# FMC.net
KiCad netlist of a schematic drawn in Altium Designer
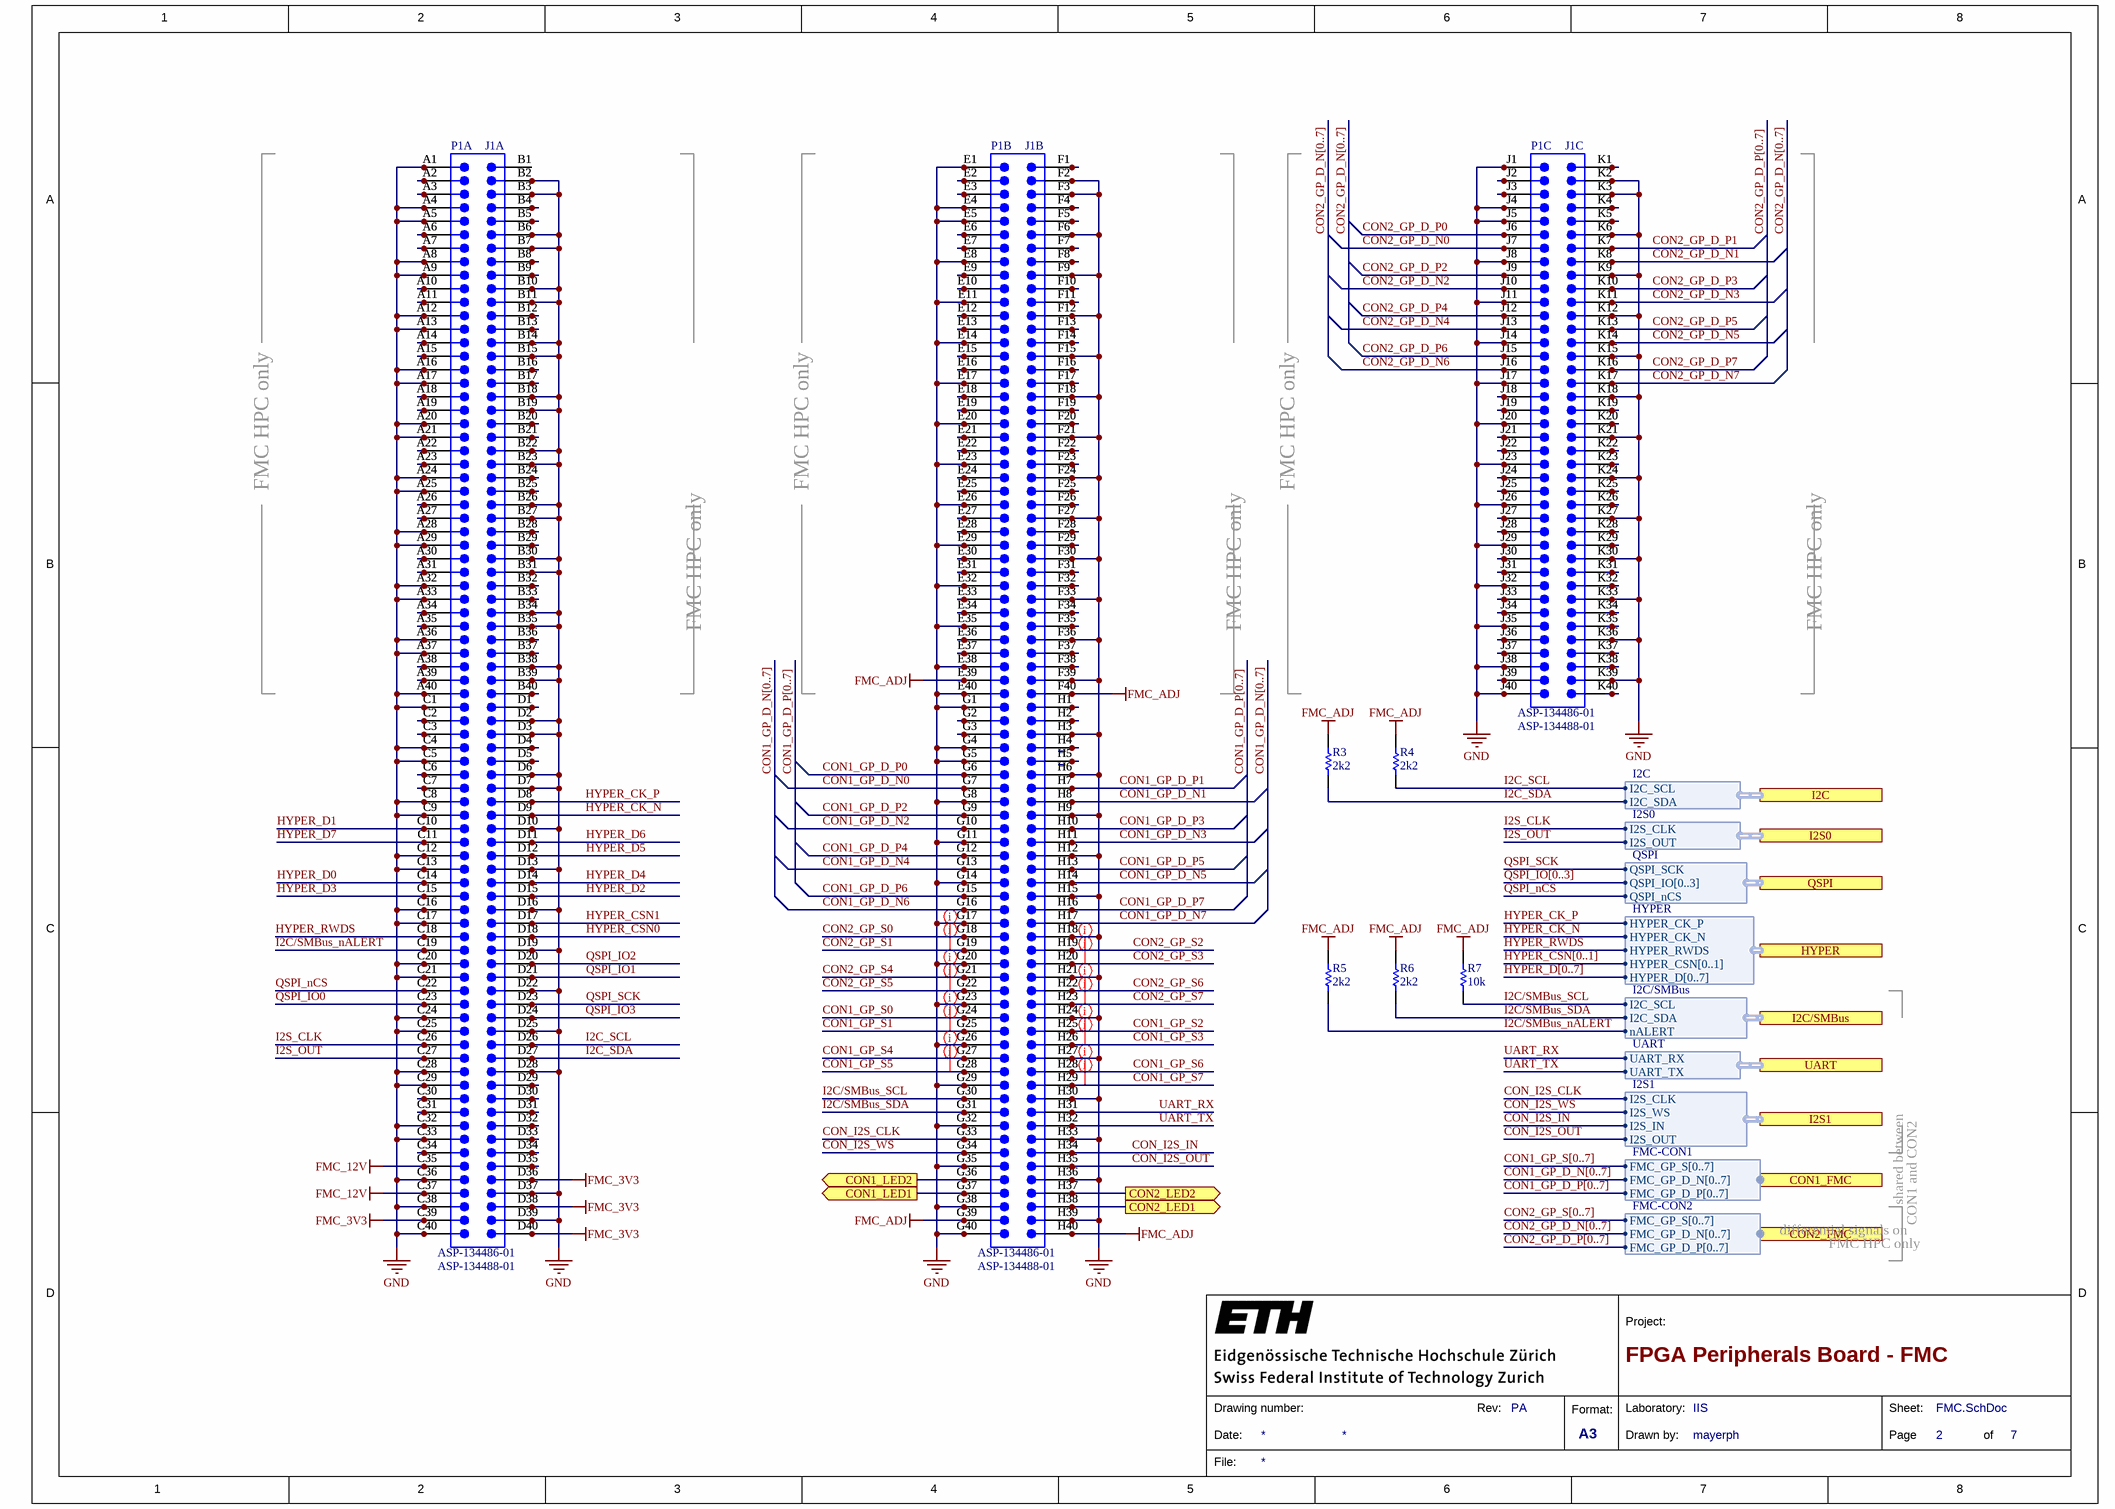
[diagram p0: FMC.SchDoc]

(export (version "E")
  (design (tool "Eeschema 10.0.6"))
  (components
    (comp (ref "J1")
      (value "ASP-134486-01")
      (footprint "BTB-SM1-27-2V400F")
      (description "Board-to-Board Connector, Vertical, 10-Row, Pitch 1.27mm, 400-Position, Female")
      (fields (field (name "MANUFACTURER") "Samtec") (field (name "PUBLISHER") "Altium"))
      (libsource (lib "Altium Content Vault") (part "CN-2P-F-R400"))
    )
    (comp (ref "P1")
      (value "ASP-134488-01")
      (footprint "BTB-SM1-27-2V400M")
      (description "Board-to-Board Connector, Vertical, 10-Row, Pitch 1.27mm, 400-Position")
      (fields (field (name "MANUFACTURER") "Samtec") (field (name "PUBLISHER") "Altium"))
      (libsource (lib "Altium Content Vault") (part "CN-2P-2M-R400"))
    )
    (comp (ref "R3")
      (value "2k2")
      (footprint "RESC1005X40X25LL05T10")
      (fields
        (field (name "MANUFACTURER") "Yageo / Phycomp")
        (field (name "PART NUMBER") "RC0402FR-072K2L")
        (field (name "TOLERANCE") "1%")
      )
      (libsource (lib "Altium Content Vault") (part "RES"))
    )
    (comp (ref "R4")
      (value "2k2")
      (footprint "RESC1005X40X25LL05T10")
      (fields
        (field (name "MANUFACTURER") "Yageo / Phycomp")
        (field (name "PART NUMBER") "RC0402FR-072K2L")
        (field (name "TOLERANCE") "1%")
      )
      (libsource (lib "Altium Content Vault") (part "RES"))
    )
    (comp (ref "R5")
      (value "2k2")
      (footprint "RESC1005X40X25LL05T10")
      (fields
        (field (name "MANUFACTURER") "Yageo / Phycomp")
        (field (name "PART NUMBER") "RC0402FR-072K2L")
        (field (name "TOLERANCE") "1%")
      )
      (libsource (lib "Altium Content Vault") (part "RES"))
    )
    (comp (ref "R6")
      (value "2k2")
      (footprint "RESC1005X40X25LL05T10")
      (fields
        (field (name "MANUFACTURER") "Yageo / Phycomp")
        (field (name "PART NUMBER") "RC0402FR-072K2L")
        (field (name "TOLERANCE") "1%")
      )
      (libsource (lib "Altium Content Vault") (part "RES"))
    )
    (comp (ref "R7")
      (value "10k")
      (footprint "RESC1005X40X25LL05T10")
      (fields
        (field (name "PART NUMBER") "RC0402FR-0710KL")
        (field (name "MANUFACTURER") "Yageo / Phycomp")
        (field (name "TOLERANCE") "1%")
      )
      (libsource (lib "Altium Content Vault") (part "RES"))
    )
  )
  (nets
    (net (code "11") (name "/CON1_GP_D_N0") (class "Default")
      (node (ref "J1") (pin "G7") (pinfunction "G7_G7") (pintype "passive"))
      (node (ref "P1") (pin "G7") (pinfunction "G7_G7") (pintype "passive"))
    )
    (net (code "12") (name "/CON1_GP_D_N1") (class "Default")
      (node (ref "J1") (pin "H8") (pinfunction "H8_H8") (pintype "passive"))
      (node (ref "P1") (pin "H8") (pinfunction "H8_H8") (pintype "passive"))
    )
    (net (code "13") (name "/CON1_GP_D_N2") (class "Default")
      (node (ref "J1") (pin "G10") (pinfunction "G10_G10") (pintype "passive"))
      (node (ref "P1") (pin "G10") (pinfunction "G10_G10") (pintype "passive"))
    )
    (net (code "14") (name "/CON1_GP_D_N3") (class "Default")
      (node (ref "J1") (pin "H11") (pinfunction "H11_H11") (pintype "passive"))
      (node (ref "P1") (pin "H11") (pinfunction "H11_H11") (pintype "passive"))
    )
    (net (code "15") (name "/CON1_GP_D_N4") (class "Default")
      (node (ref "J1") (pin "G13") (pinfunction "G13_G13") (pintype "passive"))
      (node (ref "P1") (pin "G13") (pinfunction "G13_G13") (pintype "passive"))
    )
    (net (code "16") (name "/CON1_GP_D_N5") (class "Default")
      (node (ref "J1") (pin "H14") (pinfunction "H14_H14") (pintype "passive"))
      (node (ref "P1") (pin "H14") (pinfunction "H14_H14") (pintype "passive"))
    )
    (net (code "17") (name "/CON1_GP_D_N6") (class "Default")
      (node (ref "J1") (pin "G16") (pinfunction "G16_G16") (pintype "passive"))
      (node (ref "P1") (pin "G16") (pinfunction "G16_G16") (pintype "passive"))
    )
    (net (code "18") (name "/CON1_GP_D_N7") (class "Default")
      (node (ref "J1") (pin "H17") (pinfunction "H17_H17") (pintype "passive"))
      (node (ref "P1") (pin "H17") (pinfunction "H17_H17") (pintype "passive"))
    )
    (net (code "20") (name "/CON1_GP_D_P0") (class "Default")
      (node (ref "J1") (pin "G6") (pinfunction "G6_G6") (pintype "passive"))
      (node (ref "P1") (pin "G6") (pinfunction "G6_G6") (pintype "passive"))
    )
    (net (code "21") (name "/CON1_GP_D_P1") (class "Default")
      (node (ref "J1") (pin "H7") (pinfunction "H7_H7") (pintype "passive"))
      (node (ref "P1") (pin "H7") (pinfunction "H7_H7") (pintype "passive"))
    )
    (net (code "22") (name "/CON1_GP_D_P2") (class "Default")
      (node (ref "J1") (pin "G9") (pinfunction "G9_G9") (pintype "passive"))
      (node (ref "P1") (pin "G9") (pinfunction "G9_G9") (pintype "passive"))
    )
    (net (code "23") (name "/CON1_GP_D_P3") (class "Default")
      (node (ref "J1") (pin "H10") (pinfunction "H10_H10") (pintype "passive"))
      (node (ref "P1") (pin "H10") (pinfunction "H10_H10") (pintype "passive"))
    )
    (net (code "24") (name "/CON1_GP_D_P4") (class "Default")
      (node (ref "J1") (pin "G12") (pinfunction "G12_G12") (pintype "passive"))
      (node (ref "P1") (pin "G12") (pinfunction "G12_G12") (pintype "passive"))
    )
    (net (code "25") (name "/CON1_GP_D_P5") (class "Default")
      (node (ref "J1") (pin "H13") (pinfunction "H13_H13") (pintype "passive"))
      (node (ref "P1") (pin "H13") (pinfunction "H13_H13") (pintype "passive"))
    )
    (net (code "26") (name "/CON1_GP_D_P6") (class "Default")
      (node (ref "J1") (pin "G15") (pinfunction "G15_G15") (pintype "passive"))
      (node (ref "P1") (pin "G15") (pinfunction "G15_G15") (pintype "passive"))
    )
    (net (code "27") (name "/CON1_GP_D_P7") (class "Default")
      (node (ref "J1") (pin "H16") (pinfunction "H16_H16") (pintype "passive"))
      (node (ref "P1") (pin "H16") (pinfunction "H16_H16") (pintype "passive"))
    )
    (net (code "29") (name "/CON1_GP_S0") (class "Default")
      (node (ref "J1") (pin "G24") (pinfunction "G24_G24") (pintype "passive"))
      (node (ref "P1") (pin "G24") (pinfunction "G24_G24") (pintype "passive"))
    )
    (net (code "30") (name "/CON1_GP_S1") (class "Default")
      (node (ref "J1") (pin "G25") (pinfunction "G25_G25") (pintype "passive"))
      (node (ref "P1") (pin "G25") (pinfunction "G25_G25") (pintype "passive"))
    )
    (net (code "31") (name "/CON1_GP_S2") (class "Default")
      (node (ref "J1") (pin "H25") (pinfunction "H25_H25") (pintype "passive"))
      (node (ref "P1") (pin "H25") (pinfunction "H25_H25") (pintype "passive"))
    )
    (net (code "32") (name "/CON1_GP_S3") (class "Default")
      (node (ref "J1") (pin "H26") (pinfunction "H26_H26") (pintype "passive"))
      (node (ref "P1") (pin "H26") (pinfunction "H26_H26") (pintype "passive"))
    )
    (net (code "33") (name "/CON1_GP_S4") (class "Default")
      (node (ref "J1") (pin "G27") (pinfunction "G27_G27") (pintype "passive"))
      (node (ref "P1") (pin "G27") (pinfunction "G27_G27") (pintype "passive"))
    )
    (net (code "34") (name "/CON1_GP_S5") (class "Default")
      (node (ref "J1") (pin "G28") (pinfunction "G28_G28") (pintype "passive"))
      (node (ref "P1") (pin "G28") (pinfunction "G28_G28") (pintype "passive"))
    )
    (net (code "35") (name "/CON1_GP_S6") (class "Default")
      (node (ref "J1") (pin "H28") (pinfunction "H28_H28") (pintype "passive"))
      (node (ref "P1") (pin "H28") (pinfunction "H28_H28") (pintype "passive"))
    )
    (net (code "36") (name "/CON1_GP_S7") (class "Default")
      (node (ref "J1") (pin "H29") (pinfunction "H29_H29") (pintype "passive"))
      (node (ref "P1") (pin "H29") (pinfunction "H29_H29") (pintype "passive"))
    )
    (net (code "38") (name "/CON1_LED1") (class "Default")
      (node (ref "J1") (pin "G37") (pinfunction "G37_G37") (pintype "passive"))
      (node (ref "P1") (pin "G37") (pinfunction "G37_G37") (pintype "passive"))
    )
    (net (code "39") (name "/CON1_LED2") (class "Default")
      (node (ref "J1") (pin "G36") (pinfunction "G36_G36") (pintype "passive"))
      (node (ref "P1") (pin "G36") (pinfunction "G36_G36") (pintype "passive"))
    )
    (net (code "41") (name "/CON2_GP_D_N0") (class "Default")
      (node (ref "J1") (pin "J7") (pinfunction "J7_J7") (pintype "passive"))
      (node (ref "P1") (pin "J7") (pinfunction "J7_J7") (pintype "passive"))
    )
    (net (code "42") (name "/CON2_GP_D_N1") (class "Default")
      (node (ref "J1") (pin "K8") (pinfunction "K8_K8") (pintype "passive"))
      (node (ref "P1") (pin "K8") (pinfunction "K8_K8") (pintype "passive"))
    )
    (net (code "43") (name "/CON2_GP_D_N2") (class "Default")
      (node (ref "J1") (pin "J10") (pinfunction "J10_J10") (pintype "passive"))
      (node (ref "P1") (pin "J10") (pinfunction "J10_J10") (pintype "passive"))
    )
    (net (code "44") (name "/CON2_GP_D_N3") (class "Default")
      (node (ref "J1") (pin "K11") (pinfunction "K11_K11") (pintype "passive"))
      (node (ref "P1") (pin "K11") (pinfunction "K11_K11") (pintype "passive"))
    )
    (net (code "45") (name "/CON2_GP_D_N4") (class "Default")
      (node (ref "J1") (pin "J13") (pinfunction "J13_J13") (pintype "passive"))
      (node (ref "P1") (pin "J13") (pinfunction "J13_J13") (pintype "passive"))
    )
    (net (code "46") (name "/CON2_GP_D_N5") (class "Default")
      (node (ref "J1") (pin "K14") (pinfunction "K14_K14") (pintype "passive"))
      (node (ref "P1") (pin "K14") (pinfunction "K14_K14") (pintype "passive"))
    )
    (net (code "47") (name "/CON2_GP_D_N6") (class "Default")
      (node (ref "J1") (pin "J16") (pinfunction "J16_J16") (pintype "passive"))
      (node (ref "P1") (pin "J16") (pinfunction "J16_J16") (pintype "passive"))
    )
    (net (code "48") (name "/CON2_GP_D_N7") (class "Default")
      (node (ref "J1") (pin "K17") (pinfunction "K17_K17") (pintype "passive"))
      (node (ref "P1") (pin "K17") (pinfunction "K17_K17") (pintype "passive"))
    )
    (net (code "50") (name "/CON2_GP_D_P0") (class "Default")
      (node (ref "J1") (pin "J6") (pinfunction "J6_J6") (pintype "passive"))
      (node (ref "P1") (pin "J6") (pinfunction "J6_J6") (pintype "passive"))
    )
    (net (code "51") (name "/CON2_GP_D_P1") (class "Default")
      (node (ref "J1") (pin "K7") (pinfunction "K7_K7") (pintype "passive"))
      (node (ref "P1") (pin "K7") (pinfunction "K7_K7") (pintype "passive"))
    )
    (net (code "52") (name "/CON2_GP_D_P2") (class "Default")
      (node (ref "J1") (pin "J9") (pinfunction "J9_J9") (pintype "passive"))
      (node (ref "P1") (pin "J9") (pinfunction "J9_J9") (pintype "passive"))
    )
    (net (code "53") (name "/CON2_GP_D_P3") (class "Default")
      (node (ref "J1") (pin "K10") (pinfunction "K10_K10") (pintype "passive"))
      (node (ref "P1") (pin "K10") (pinfunction "K10_K10") (pintype "passive"))
    )
    (net (code "54") (name "/CON2_GP_D_P4") (class "Default")
      (node (ref "J1") (pin "J12") (pinfunction "J12_J12") (pintype "passive"))
      (node (ref "P1") (pin "J12") (pinfunction "J12_J12") (pintype "passive"))
    )
    (net (code "55") (name "/CON2_GP_D_P5") (class "Default")
      (node (ref "J1") (pin "K13") (pinfunction "K13_K13") (pintype "passive"))
      (node (ref "P1") (pin "K13") (pinfunction "K13_K13") (pintype "passive"))
    )
    (net (code "56") (name "/CON2_GP_D_P6") (class "Default")
      (node (ref "J1") (pin "J15") (pinfunction "J15_J15") (pintype "passive"))
      (node (ref "P1") (pin "J15") (pinfunction "J15_J15") (pintype "passive"))
    )
    (net (code "57") (name "/CON2_GP_D_P7") (class "Default")
      (node (ref "J1") (pin "K16") (pinfunction "K16_K16") (pintype "passive"))
      (node (ref "P1") (pin "K16") (pinfunction "K16_K16") (pintype "passive"))
    )
    (net (code "59") (name "/CON2_GP_S0") (class "Default")
      (node (ref "J1") (pin "G18") (pinfunction "G18_G18") (pintype "passive"))
      (node (ref "P1") (pin "G18") (pinfunction "G18_G18") (pintype "passive"))
    )
    (net (code "60") (name "/CON2_GP_S1") (class "Default")
      (node (ref "J1") (pin "G19") (pinfunction "G19_G19") (pintype "passive"))
      (node (ref "P1") (pin "G19") (pinfunction "G19_G19") (pintype "passive"))
    )
    (net (code "61") (name "/CON2_GP_S2") (class "Default")
      (node (ref "J1") (pin "H19") (pinfunction "H19_H19") (pintype "passive"))
      (node (ref "P1") (pin "H19") (pinfunction "H19_H19") (pintype "passive"))
    )
    (net (code "62") (name "/CON2_GP_S3") (class "Default")
      (node (ref "J1") (pin "H20") (pinfunction "H20_H20") (pintype "passive"))
      (node (ref "P1") (pin "H20") (pinfunction "H20_H20") (pintype "passive"))
    )
    (net (code "63") (name "/CON2_GP_S4") (class "Default")
      (node (ref "J1") (pin "G21") (pinfunction "G21_G21") (pintype "passive"))
      (node (ref "P1") (pin "G21") (pinfunction "G21_G21") (pintype "passive"))
    )
    (net (code "64") (name "/CON2_GP_S5") (class "Default")
      (node (ref "J1") (pin "G22") (pinfunction "G22_G22") (pintype "passive"))
      (node (ref "P1") (pin "G22") (pinfunction "G22_G22") (pintype "passive"))
    )
    (net (code "65") (name "/CON2_GP_S6") (class "Default")
      (node (ref "J1") (pin "H22") (pinfunction "H22_H22") (pintype "passive"))
      (node (ref "P1") (pin "H22") (pinfunction "H22_H22") (pintype "passive"))
    )
    (net (code "66") (name "/CON2_GP_S7") (class "Default")
      (node (ref "J1") (pin "H23") (pinfunction "H23_H23") (pintype "passive"))
      (node (ref "P1") (pin "H23") (pinfunction "H23_H23") (pintype "passive"))
    )
    (net (code "68") (name "/CON2_LED1") (class "Default")
      (node (ref "J1") (pin "H38") (pinfunction "H38_H38") (pintype "passive"))
      (node (ref "P1") (pin "H38") (pinfunction "H38_H38") (pintype "passive"))
    )
    (net (code "69") (name "/CON2_LED2") (class "Default")
      (node (ref "J1") (pin "H37") (pinfunction "H37_H37") (pintype "passive"))
      (node (ref "P1") (pin "H37") (pinfunction "H37_H37") (pintype "passive"))
    )
    (net (code "70") (name "/CON_I2S_CLK") (class "Default")
      (node (ref "J1") (pin "G33") (pinfunction "G33_G33") (pintype "passive"))
      (node (ref "P1") (pin "G33") (pinfunction "G33_G33") (pintype "passive"))
    )
    (net (code "71") (name "/CON_I2S_IN") (class "Default")
      (node (ref "J1") (pin "H34") (pinfunction "H34_H34") (pintype "passive"))
      (node (ref "P1") (pin "H34") (pinfunction "H34_H34") (pintype "passive"))
    )
    (net (code "72") (name "/CON_I2S_OUT") (class "Default")
      (node (ref "J1") (pin "H35") (pinfunction "H35_H35") (pintype "passive"))
      (node (ref "P1") (pin "H35") (pinfunction "H35_H35") (pintype "passive"))
    )
    (net (code "73") (name "/CON_I2S_WS") (class "Default")
      (node (ref "J1") (pin "G34") (pinfunction "G34_G34") (pintype "passive"))
      (node (ref "P1") (pin "G34") (pinfunction "G34_G34") (pintype "passive"))
    )
    (net (code "74") (name "/HYPER_CK_N") (class "Default")
      (node (ref "J1") (pin "D9") (pinfunction "D9_D9") (pintype "passive"))
      (node (ref "P1") (pin "D9") (pinfunction "D9_D9") (pintype "passive"))
    )
    (net (code "75") (name "/HYPER_CK_P") (class "Default")
      (node (ref "J1") (pin "D8") (pinfunction "D8_D8") (pintype "passive"))
      (node (ref "P1") (pin "D8") (pinfunction "D8_D8") (pintype "passive"))
    )
    (net (code "76") (name "/HYPER_CSN0") (class "Default")
      (node (ref "J1") (pin "D18") (pinfunction "D18_D18") (pintype "passive"))
      (node (ref "P1") (pin "D18") (pinfunction "D18_D18") (pintype "passive"))
    )
    (net (code "77") (name "/HYPER_CSN1") (class "Default")
      (node (ref "J1") (pin "D17") (pinfunction "D17_D17") (pintype "passive"))
      (node (ref "P1") (pin "D17") (pinfunction "D17_D17") (pintype "passive"))
    )
    (net (code "79") (name "/HYPER_D0") (class "Default")
      (node (ref "J1") (pin "C14") (pinfunction "C14_C14") (pintype "passive"))
      (node (ref "P1") (pin "C14") (pinfunction "C14_C14") (pintype "passive"))
    )
    (net (code "80") (name "/HYPER_D1") (class "Default")
      (node (ref "J1") (pin "C10") (pinfunction "C10_C10") (pintype "passive"))
      (node (ref "P1") (pin "C10") (pinfunction "C10_C10") (pintype "passive"))
    )
    (net (code "81") (name "/HYPER_D2") (class "Default")
      (node (ref "J1") (pin "D15") (pinfunction "D15_D15") (pintype "passive"))
      (node (ref "P1") (pin "D15") (pinfunction "D15_D15") (pintype "passive"))
    )
    (net (code "82") (name "/HYPER_D3") (class "Default")
      (node (ref "J1") (pin "C15") (pinfunction "C15_C15") (pintype "passive"))
      (node (ref "P1") (pin "C15") (pinfunction "C15_C15") (pintype "passive"))
    )
    (net (code "83") (name "/HYPER_D4") (class "Default")
      (node (ref "J1") (pin "D14") (pinfunction "D14_D14") (pintype "passive"))
      (node (ref "P1") (pin "D14") (pinfunction "D14_D14") (pintype "passive"))
    )
    (net (code "84") (name "/HYPER_D5") (class "Default")
      (node (ref "J1") (pin "D12") (pinfunction "D12_D12") (pintype "passive"))
      (node (ref "P1") (pin "D12") (pinfunction "D12_D12") (pintype "passive"))
    )
    (net (code "85") (name "/HYPER_D6") (class "Default")
      (node (ref "J1") (pin "D11") (pinfunction "D11_D11") (pintype "passive"))
      (node (ref "P1") (pin "D11") (pinfunction "D11_D11") (pintype "passive"))
    )
    (net (code "86") (name "/HYPER_D7") (class "Default")
      (node (ref "J1") (pin "C11") (pinfunction "C11_C11") (pintype "passive"))
      (node (ref "P1") (pin "C11") (pinfunction "C11_C11") (pintype "passive"))
    )
    (net (code "88") (name "/HYPER_RWDS") (class "Default")
      (node (ref "J1") (pin "C18") (pinfunction "C18_C18") (pintype "passive"))
      (node (ref "P1") (pin "C18") (pinfunction "C18_C18") (pintype "passive"))
    )
    (net (code "89") (name "/I2C_SCL") (class "Default")
      (node (ref "J1") (pin "D26") (pinfunction "D26_D26") (pintype "passive"))
      (node (ref "P1") (pin "D26") (pinfunction "D26_D26") (pintype "passive"))
      (node (ref "R4") (pin "1") (pinfunction "1_1") (pintype "passive"))
    )
    (net (code "90") (name "/I2C_SDA") (class "Default")
      (node (ref "J1") (pin "D27") (pinfunction "D27_D27") (pintype "passive"))
      (node (ref "P1") (pin "D27") (pinfunction "D27_D27") (pintype "passive"))
      (node (ref "R3") (pin "1") (pinfunction "1_1") (pintype "passive"))
    )
    (net (code "91") (name "/I2C{slash}SMBus_SCL") (class "Default")
      (node (ref "J1") (pin "G30") (pinfunction "G30_G30") (pintype "passive"))
      (node (ref "P1") (pin "G30") (pinfunction "G30_G30") (pintype "passive"))
      (node (ref "R7") (pin "1") (pinfunction "1_1") (pintype "passive"))
    )
    (net (code "92") (name "/I2C{slash}SMBus_SDA") (class "Default")
      (node (ref "J1") (pin "G31") (pinfunction "G31_G31") (pintype "passive"))
      (node (ref "P1") (pin "G31") (pinfunction "G31_G31") (pintype "passive"))
      (node (ref "R6") (pin "1") (pinfunction "1_1") (pintype "passive"))
    )
    (net (code "93") (name "/I2C{slash}SMBus_nALERT") (class "Default")
      (node (ref "J1") (pin "C19") (pinfunction "C19_C19") (pintype "passive"))
      (node (ref "P1") (pin "C19") (pinfunction "C19_C19") (pintype "passive"))
      (node (ref "R5") (pin "1") (pinfunction "1_1") (pintype "passive"))
    )
    (net (code "94") (name "/I2S_CLK") (class "Default")
      (node (ref "J1") (pin "C26") (pinfunction "C26_C26") (pintype "passive"))
      (node (ref "P1") (pin "C26") (pinfunction "C26_C26") (pintype "passive"))
    )
    (net (code "95") (name "/I2S_OUT") (class "Default")
      (node (ref "J1") (pin "C27") (pinfunction "C27_C27") (pintype "passive"))
      (node (ref "P1") (pin "C27") (pinfunction "C27_C27") (pintype "passive"))
    )
    (net (code "96") (name "/QSPI_IO0") (class "Default")
      (node (ref "J1") (pin "C23") (pinfunction "C23_C23") (pintype "passive"))
      (node (ref "P1") (pin "C23") (pinfunction "C23_C23") (pintype "passive"))
    )
    (net (code "97") (name "/QSPI_IO1") (class "Default")
      (node (ref "J1") (pin "D21") (pinfunction "D21_D21") (pintype "passive"))
      (node (ref "P1") (pin "D21") (pinfunction "D21_D21") (pintype "passive"))
    )
    (net (code "98") (name "/QSPI_IO2") (class "Default")
      (node (ref "J1") (pin "D20") (pinfunction "D20_D20") (pintype "passive"))
      (node (ref "P1") (pin "D20") (pinfunction "D20_D20") (pintype "passive"))
    )
    (net (code "99") (name "/QSPI_IO3") (class "Default")
      (node (ref "J1") (pin "D24") (pinfunction "D24_D24") (pintype "passive"))
      (node (ref "P1") (pin "D24") (pinfunction "D24_D24") (pintype "passive"))
    )
    (net (code "101") (name "/QSPI_SCK") (class "Default")
      (node (ref "J1") (pin "D23") (pinfunction "D23_D23") (pintype "passive"))
      (node (ref "P1") (pin "D23") (pinfunction "D23_D23") (pintype "passive"))
    )
    (net (code "102") (name "/QSPI_nCS") (class "Default")
      (node (ref "J1") (pin "C22") (pinfunction "C22_C22") (pintype "passive"))
      (node (ref "P1") (pin "C22") (pinfunction "C22_C22") (pintype "passive"))
    )
    (net (code "103") (name "/UART_RX") (class "Default")
      (node (ref "J1") (pin "H31") (pinfunction "H31_H31") (pintype "passive"))
      (node (ref "P1") (pin "H31") (pinfunction "H31_H31") (pintype "passive"))
    )
    (net (code "104") (name "/UART_TX") (class "Default")
      (node (ref "J1") (pin "H32") (pinfunction "H32_H32") (pintype "passive"))
      (node (ref "P1") (pin "H32") (pinfunction "H32_H32") (pintype "passive"))
    )
    (net (code "112") (name "FMC_3V3") (class "Default")
      (node (ref "J1") (pin "C39") (pinfunction "C39_C39") (pintype "passive"))
      (node (ref "J1") (pin "D36") (pinfunction "D36_D36") (pintype "passive"))
      (node (ref "J1") (pin "D38") (pinfunction "D38_D38") (pintype "passive"))
      (node (ref "J1") (pin "D40") (pinfunction "D40_D40") (pintype "passive"))
      (node (ref "P1") (pin "C39") (pinfunction "C39_C39") (pintype "passive"))
      (node (ref "P1") (pin "D36") (pinfunction "D36_D36") (pintype "passive"))
      (node (ref "P1") (pin "D38") (pinfunction "D38_D38") (pintype "passive"))
      (node (ref "P1") (pin "D40") (pinfunction "D40_D40") (pintype "passive"))
    )
    (net (code "113") (name "FMC_12V") (class "Default")
      (node (ref "J1") (pin "C35") (pinfunction "C35_C35") (pintype "passive"))
      (node (ref "J1") (pin "C37") (pinfunction "C37_C37") (pintype "passive"))
      (node (ref "P1") (pin "C35") (pinfunction "C35_C35") (pintype "passive"))
      (node (ref "P1") (pin "C37") (pinfunction "C37_C37") (pintype "passive"))
    )
    (net (code "114") (name "FMC_ADJ") (class "Default")
      (node (ref "J1") (pin "E39") (pinfunction "E39_E39") (pintype "passive"))
      (node (ref "J1") (pin "F40") (pinfunction "F40_F40") (pintype "passive"))
      (node (ref "J1") (pin "G39") (pinfunction "G39_G39") (pintype "passive"))
      (node (ref "J1") (pin "H40") (pinfunction "H40_H40") (pintype "passive"))
      (node (ref "P1") (pin "E39") (pinfunction "E39_E39") (pintype "passive"))
      (node (ref "P1") (pin "F40") (pinfunction "F40_F40") (pintype "passive"))
      (node (ref "P1") (pin "G39") (pinfunction "G39_G39") (pintype "passive"))
      (node (ref "P1") (pin "H40") (pinfunction "H40_H40") (pintype "passive"))
      (node (ref "R3") (pin "2") (pinfunction "2_2") (pintype "passive"))
      (node (ref "R4") (pin "2") (pinfunction "2_2") (pintype "passive"))
      (node (ref "R5") (pin "2") (pinfunction "2_2") (pintype "passive"))
      (node (ref "R6") (pin "2") (pinfunction "2_2") (pintype "passive"))
      (node (ref "R7") (pin "2") (pinfunction "2_2") (pintype "passive"))
    )
    (net (code "115") (name "GND") (class "Default")
      (node (ref "J1") (pin "A1") (pinfunction "A1_A1") (pintype "passive"))
      (node (ref "J1") (pin "A12") (pinfunction "A12_A12") (pintype "passive"))
      (node (ref "J1") (pin "A13") (pinfunction "A13_A13") (pintype "passive"))
      (node (ref "J1") (pin "A16") (pinfunction "A16_A16") (pintype "passive"))
      (node (ref "J1") (pin "A17") (pinfunction "A17_A17") (pintype "passive"))
      (node (ref "J1") (pin "A20") (pinfunction "A20_A20") (pintype "passive"))
      (node (ref "J1") (pin "A21") (pinfunction "A21_A21") (pintype "passive"))
      (node (ref "J1") (pin "A24") (pinfunction "A24_A24") (pintype "passive"))
      (node (ref "J1") (pin "A25") (pinfunction "A25_A25") (pintype "passive"))
      (node (ref "J1") (pin "A28") (pinfunction "A28_A28") (pintype "passive"))
      (node (ref "J1") (pin "A29") (pinfunction "A29_A29") (pintype "passive"))
      (node (ref "J1") (pin "A32") (pinfunction "A32_A32") (pintype "passive"))
      (node (ref "J1") (pin "A33") (pinfunction "A33_A33") (pintype "passive"))
      (node (ref "J1") (pin "A36") (pinfunction "A36_A36") (pintype "passive"))
      (node (ref "J1") (pin "A37") (pinfunction "A37_A37") (pintype "passive"))
      (node (ref "J1") (pin "A4") (pinfunction "A4_A4") (pintype "passive"))
      (node (ref "J1") (pin "A40") (pinfunction "A40_A40") (pintype "passive"))
      (node (ref "J1") (pin "A5") (pinfunction "A5_A5") (pintype "passive"))
      (node (ref "J1") (pin "A8") (pinfunction "A8_A8") (pintype "passive"))
      (node (ref "J1") (pin "A9") (pinfunction "A9_A9") (pintype "passive"))
      (node (ref "J1") (pin "B10") (pinfunction "B10_B10") (pintype "passive"))
      (node (ref "J1") (pin "B11") (pinfunction "B11_B11") (pintype "passive"))
      (node (ref "J1") (pin "B14") (pinfunction "B14_B14") (pintype "passive"))
      (node (ref "J1") (pin "B15") (pinfunction "B15_B15") (pintype "passive"))
      (node (ref "J1") (pin "B18") (pinfunction "B18_B18") (pintype "passive"))
      (node (ref "J1") (pin "B19") (pinfunction "B19_B19") (pintype "passive"))
      (node (ref "J1") (pin "B2") (pinfunction "B2_B2") (pintype "passive"))
      (node (ref "J1") (pin "B22") (pinfunction "B22_B22") (pintype "passive"))
      (node (ref "J1") (pin "B23") (pinfunction "B23_B23") (pintype "passive"))
      (node (ref "J1") (pin "B26") (pinfunction "B26_B26") (pintype "passive"))
      (node (ref "J1") (pin "B27") (pinfunction "B27_B27") (pintype "passive"))
      (node (ref "J1") (pin "B3") (pinfunction "B3_B3") (pintype "passive"))
      (node (ref "J1") (pin "B30") (pinfunction "B30_B30") (pintype "passive"))
      (node (ref "J1") (pin "B31") (pinfunction "B31_B31") (pintype "passive"))
      (node (ref "J1") (pin "B34") (pinfunction "B34_B34") (pintype "passive"))
      (node (ref "J1") (pin "B35") (pinfunction "B35_B35") (pintype "passive"))
      (node (ref "J1") (pin "B38") (pinfunction "B38_B38") (pintype "passive"))
      (node (ref "J1") (pin "B39") (pinfunction "B39_B39") (pintype "passive"))
      (node (ref "J1") (pin "B6") (pinfunction "B6_B6") (pintype "passive"))
      (node (ref "J1") (pin "B7") (pinfunction "B7_B7") (pintype "passive"))
      (node (ref "J1") (pin "C1") (pinfunction "C1_C1") (pintype "passive"))
      (node (ref "J1") (pin "C12") (pinfunction "C12_C12") (pintype "passive"))
      (node (ref "J1") (pin "C13") (pinfunction "C13_C13") (pintype "passive"))
      (node (ref "J1") (pin "C16") (pinfunction "C16_C16") (pintype "passive"))
      (node (ref "J1") (pin "C17") (pinfunction "C17_C17") (pintype "passive"))
      (node (ref "J1") (pin "C20") (pinfunction "C20_C20") (pintype "passive"))
      (node (ref "J1") (pin "C21") (pinfunction "C21_C21") (pintype "passive"))
      (node (ref "J1") (pin "C24") (pinfunction "C24_C24") (pintype "passive"))
      (node (ref "J1") (pin "C25") (pinfunction "C25_C25") (pintype "passive"))
      (node (ref "J1") (pin "C28") (pinfunction "C28_C28") (pintype "passive"))
      (node (ref "J1") (pin "C29") (pinfunction "C29_C29") (pintype "passive"))
      (node (ref "J1") (pin "C32") (pinfunction "C32_C32") (pintype "passive"))
      (node (ref "J1") (pin "C33") (pinfunction "C33_C33") (pintype "passive"))
      (node (ref "J1") (pin "C36") (pinfunction "C36_C36") (pintype "passive"))
      (node (ref "J1") (pin "C38") (pinfunction "C38_C38") (pintype "passive"))
      (node (ref "J1") (pin "C4") (pinfunction "C4_C4") (pintype "passive"))
      (node (ref "J1") (pin "C40") (pinfunction "C40_C40") (pintype "passive"))
      (node (ref "J1") (pin "C5") (pinfunction "C5_C5") (pintype "passive"))
      (node (ref "J1") (pin "C8") (pinfunction "C8_C8") (pintype "passive"))
      (node (ref "J1") (pin "C9") (pinfunction "C9_C9") (pintype "passive"))
      (node (ref "J1") (pin "D10") (pinfunction "D10_D10") (pintype "passive"))
      (node (ref "J1") (pin "D13") (pinfunction "D13_D13") (pintype "passive"))
      (node (ref "J1") (pin "D16") (pinfunction "D16_D16") (pintype "passive"))
      (node (ref "J1") (pin "D19") (pinfunction "D19_D19") (pintype "passive"))
      (node (ref "J1") (pin "D2") (pinfunction "D2_D2") (pintype "passive"))
      (node (ref "J1") (pin "D22") (pinfunction "D22_D22") (pintype "passive"))
      (node (ref "J1") (pin "D25") (pinfunction "D25_D25") (pintype "passive"))
      (node (ref "J1") (pin "D28") (pinfunction "D28_D28") (pintype "passive"))
      (node (ref "J1") (pin "D3") (pinfunction "D3_D3") (pintype "passive"))
      (node (ref "J1") (pin "D37") (pinfunction "D37_D37") (pintype "passive"))
      (node (ref "J1") (pin "D39") (pinfunction "D39_D39") (pintype "passive"))
      (node (ref "J1") (pin "D6") (pinfunction "D6_D6") (pintype "passive"))
      (node (ref "J1") (pin "D7") (pinfunction "D7_D7") (pintype "passive"))
      (node (ref "J1") (pin "E1") (pinfunction "E1_E1") (pintype "passive"))
      (node (ref "J1") (pin "E11") (pinfunction "E11_E11") (pintype "passive"))
      (node (ref "J1") (pin "E14") (pinfunction "E14_E14") (pintype "passive"))
      (node (ref "J1") (pin "E17") (pinfunction "E17_E17") (pintype "passive"))
      (node (ref "J1") (pin "E20") (pinfunction "E20_E20") (pintype "passive"))
      (node (ref "J1") (pin "E23") (pinfunction "E23_E23") (pintype "passive"))
      (node (ref "J1") (pin "E26") (pinfunction "E26_E26") (pintype "passive"))
      (node (ref "J1") (pin "E29") (pinfunction "E29_E29") (pintype "passive"))
      (node (ref "J1") (pin "E32") (pinfunction "E32_E32") (pintype "passive"))
      (node (ref "J1") (pin "E35") (pinfunction "E35_E35") (pintype "passive"))
      (node (ref "J1") (pin "E38") (pinfunction "E38_E38") (pintype "passive"))
      (node (ref "J1") (pin "E4") (pinfunction "E4_E4") (pintype "passive"))
      (node (ref "J1") (pin "E40") (pinfunction "E40_E40") (pintype "passive"))
      (node (ref "J1") (pin "E5") (pinfunction "E5_E5") (pintype "passive"))
      (node (ref "J1") (pin "E8") (pinfunction "E8_E8") (pintype "passive"))
      (node (ref "J1") (pin "F12") (pinfunction "F12_F12") (pintype "passive"))
      (node (ref "J1") (pin "F15") (pinfunction "F15_F15") (pintype "passive"))
      (node (ref "J1") (pin "F18") (pinfunction "F18_F18") (pintype "passive"))
      (node (ref "J1") (pin "F2") (pinfunction "F2_F2") (pintype "passive"))
      (node (ref "J1") (pin "F21") (pinfunction "F21_F21") (pintype "passive"))
      (node (ref "J1") (pin "F24") (pinfunction "F24_F24") (pintype "passive"))
      (node (ref "J1") (pin "F27") (pinfunction "F27_F27") (pintype "passive"))
      (node (ref "J1") (pin "F3") (pinfunction "F3_F3") (pintype "passive"))
      (node (ref "J1") (pin "F30") (pinfunction "F30_F30") (pintype "passive"))
      (node (ref "J1") (pin "F33") (pinfunction "F33_F33") (pintype "passive"))
      (node (ref "J1") (pin "F36") (pinfunction "F36_F36") (pintype "passive"))
      (node (ref "J1") (pin "F39") (pinfunction "F39_F39") (pintype "passive"))
      (node (ref "J1") (pin "F6") (pinfunction "F6_F6") (pintype "passive"))
      (node (ref "J1") (pin "F9") (pinfunction "F9_F9") (pintype "passive"))
      (node (ref "J1") (pin "G1") (pinfunction "G1_G1") (pintype "passive"))
      (node (ref "J1") (pin "G11") (pinfunction "G11_G11") (pintype "passive"))
      (node (ref "J1") (pin "G14") (pinfunction "G14_G14") (pintype "passive"))
      (node (ref "J1") (pin "G17") (pinfunction "G17_G17") (pintype "passive"))
      (node (ref "J1") (pin "G20") (pinfunction "G20_G20") (pintype "passive"))
      (node (ref "J1") (pin "G23") (pinfunction "G23_G23") (pintype "passive"))
      (node (ref "J1") (pin "G26") (pinfunction "G26_G26") (pintype "passive"))
      (node (ref "J1") (pin "G29") (pinfunction "G29_G29") (pintype "passive"))
      (node (ref "J1") (pin "G32") (pinfunction "G32_G32") (pintype "passive"))
      (node (ref "J1") (pin "G35") (pinfunction "G35_G35") (pintype "passive"))
      (node (ref "J1") (pin "G38") (pinfunction "G38_G38") (pintype "passive"))
      (node (ref "J1") (pin "G4") (pinfunction "G4_G4") (pintype "passive"))
      (node (ref "J1") (pin "G40") (pinfunction "G40_G40") (pintype "passive"))
      (node (ref "J1") (pin "G5") (pinfunction "G5_G5") (pintype "passive"))
      (node (ref "J1") (pin "G8") (pinfunction "G8_G8") (pintype "passive"))
      (node (ref "J1") (pin "H12") (pinfunction "H12_H12") (pintype "passive"))
      (node (ref "J1") (pin "H15") (pinfunction "H15_H15") (pintype "passive"))
      (node (ref "J1") (pin "H18") (pinfunction "H18_H18") (pintype "passive"))
      (node (ref "J1") (pin "H21") (pinfunction "H21_H21") (pintype "passive"))
      (node (ref "J1") (pin "H24") (pinfunction "H24_H24") (pintype "passive"))
      (node (ref "J1") (pin "H27") (pinfunction "H27_H27") (pintype "passive"))
      (node (ref "J1") (pin "H3") (pinfunction "H3_H3") (pintype "passive"))
      (node (ref "J1") (pin "H30") (pinfunction "H30_H30") (pintype "passive"))
      (node (ref "J1") (pin "H33") (pinfunction "H33_H33") (pintype "passive"))
      (node (ref "J1") (pin "H36") (pinfunction "H36_H36") (pintype "passive"))
      (node (ref "J1") (pin "H39") (pinfunction "H39_H39") (pintype "passive"))
      (node (ref "J1") (pin "H6") (pinfunction "H6_H6") (pintype "passive"))
      (node (ref "J1") (pin "H9") (pinfunction "H9_H9") (pintype "passive"))
      (node (ref "J1") (pin "J1") (pinfunction "J1_J1") (pintype "passive"))
      (node (ref "J1") (pin "J11") (pinfunction "J11_J11") (pintype "passive"))
      (node (ref "J1") (pin "J14") (pinfunction "J14_J14") (pintype "passive"))
      (node (ref "J1") (pin "J17") (pinfunction "J17_J17") (pintype "passive"))
      (node (ref "J1") (pin "J20") (pinfunction "J20_J20") (pintype "passive"))
      (node (ref "J1") (pin "J23") (pinfunction "J23_J23") (pintype "passive"))
      (node (ref "J1") (pin "J26") (pinfunction "J26_J26") (pintype "passive"))
      (node (ref "J1") (pin "J29") (pinfunction "J29_J29") (pintype "passive"))
      (node (ref "J1") (pin "J32") (pinfunction "J32_J32") (pintype "passive"))
      (node (ref "J1") (pin "J35") (pinfunction "J35_J35") (pintype "passive"))
      (node (ref "J1") (pin "J38") (pinfunction "J38_J38") (pintype "passive"))
      (node (ref "J1") (pin "J4") (pinfunction "J4_J4") (pintype "passive"))
      (node (ref "J1") (pin "J40") (pinfunction "J40_J40") (pintype "passive"))
      (node (ref "J1") (pin "J5") (pinfunction "J5_J5") (pintype "passive"))
      (node (ref "J1") (pin "J8") (pinfunction "J8_J8") (pintype "passive"))
      (node (ref "J1") (pin "K12") (pinfunction "K12_K12") (pintype "passive"))
      (node (ref "J1") (pin "K15") (pinfunction "K15_K15") (pintype "passive"))
      (node (ref "J1") (pin "K18") (pinfunction "K18_K18") (pintype "passive"))
      (node (ref "J1") (pin "K2") (pinfunction "K2_K2") (pintype "passive"))
      (node (ref "J1") (pin "K21") (pinfunction "K21_K21") (pintype "passive"))
      (node (ref "J1") (pin "K24") (pinfunction "K24_K24") (pintype "passive"))
      (node (ref "J1") (pin "K27") (pinfunction "K27_K27") (pintype "passive"))
      (node (ref "J1") (pin "K3") (pinfunction "K3_K3") (pintype "passive"))
      (node (ref "J1") (pin "K30") (pinfunction "K30_K30") (pintype "passive"))
      (node (ref "J1") (pin "K33") (pinfunction "K33_K33") (pintype "passive"))
      (node (ref "J1") (pin "K36") (pinfunction "K36_K36") (pintype "passive"))
      (node (ref "J1") (pin "K39") (pinfunction "K39_K39") (pintype "passive"))
      (node (ref "J1") (pin "K6") (pinfunction "K6_K6") (pintype "passive"))
      (node (ref "J1") (pin "K9") (pinfunction "K9_K9") (pintype "passive"))
      (node (ref "P1") (pin "A1") (pinfunction "A1_A1") (pintype "passive"))
      (node (ref "P1") (pin "A12") (pinfunction "A12_A12") (pintype "passive"))
      (node (ref "P1") (pin "A13") (pinfunction "A13_A13") (pintype "passive"))
      (node (ref "P1") (pin "A16") (pinfunction "A16_A16") (pintype "passive"))
      (node (ref "P1") (pin "A17") (pinfunction "A17_A17") (pintype "passive"))
      (node (ref "P1") (pin "A20") (pinfunction "A20_A20") (pintype "passive"))
      (node (ref "P1") (pin "A21") (pinfunction "A21_A21") (pintype "passive"))
      (node (ref "P1") (pin "A24") (pinfunction "A24_A24") (pintype "passive"))
      (node (ref "P1") (pin "A25") (pinfunction "A25_A25") (pintype "passive"))
      (node (ref "P1") (pin "A28") (pinfunction "A28_A28") (pintype "passive"))
      (node (ref "P1") (pin "A29") (pinfunction "A29_A29") (pintype "passive"))
      (node (ref "P1") (pin "A32") (pinfunction "A32_A32") (pintype "passive"))
      (node (ref "P1") (pin "A33") (pinfunction "A33_A33") (pintype "passive"))
      (node (ref "P1") (pin "A36") (pinfunction "A36_A36") (pintype "passive"))
      (node (ref "P1") (pin "A37") (pinfunction "A37_A37") (pintype "passive"))
      (node (ref "P1") (pin "A4") (pinfunction "A4_A4") (pintype "passive"))
      (node (ref "P1") (pin "A40") (pinfunction "A40_A40") (pintype "passive"))
      (node (ref "P1") (pin "A5") (pinfunction "A5_A5") (pintype "passive"))
      (node (ref "P1") (pin "A8") (pinfunction "A8_A8") (pintype "passive"))
      (node (ref "P1") (pin "A9") (pinfunction "A9_A9") (pintype "passive"))
      (node (ref "P1") (pin "B10") (pinfunction "B10_B10") (pintype "passive"))
      (node (ref "P1") (pin "B11") (pinfunction "B11_B11") (pintype "passive"))
      (node (ref "P1") (pin "B14") (pinfunction "B14_B14") (pintype "passive"))
      (node (ref "P1") (pin "B15") (pinfunction "B15_B15") (pintype "passive"))
      (node (ref "P1") (pin "B18") (pinfunction "B18_B18") (pintype "passive"))
      (node (ref "P1") (pin "B19") (pinfunction "B19_B19") (pintype "passive"))
      (node (ref "P1") (pin "B2") (pinfunction "B2_B2") (pintype "passive"))
      (node (ref "P1") (pin "B22") (pinfunction "B22_B22") (pintype "passive"))
      (node (ref "P1") (pin "B23") (pinfunction "B23_B23") (pintype "passive"))
      (node (ref "P1") (pin "B26") (pinfunction "B26_B26") (pintype "passive"))
      (node (ref "P1") (pin "B27") (pinfunction "B27_B27") (pintype "passive"))
      (node (ref "P1") (pin "B3") (pinfunction "B3_B3") (pintype "passive"))
      (node (ref "P1") (pin "B30") (pinfunction "B30_B30") (pintype "passive"))
      (node (ref "P1") (pin "B31") (pinfunction "B31_B31") (pintype "passive"))
      (node (ref "P1") (pin "B34") (pinfunction "B34_B34") (pintype "passive"))
      (node (ref "P1") (pin "B35") (pinfunction "B35_B35") (pintype "passive"))
      (node (ref "P1") (pin "B38") (pinfunction "B38_B38") (pintype "passive"))
      (node (ref "P1") (pin "B39") (pinfunction "B39_B39") (pintype "passive"))
      (node (ref "P1") (pin "B6") (pinfunction "B6_B6") (pintype "passive"))
      (node (ref "P1") (pin "B7") (pinfunction "B7_B7") (pintype "passive"))
      (node (ref "P1") (pin "C1") (pinfunction "C1_C1") (pintype "passive"))
      (node (ref "P1") (pin "C12") (pinfunction "C12_C12") (pintype "passive"))
      (node (ref "P1") (pin "C13") (pinfunction "C13_C13") (pintype "passive"))
      (node (ref "P1") (pin "C16") (pinfunction "C16_C16") (pintype "passive"))
      (node (ref "P1") (pin "C17") (pinfunction "C17_C17") (pintype "passive"))
      (node (ref "P1") (pin "C20") (pinfunction "C20_C20") (pintype "passive"))
      (node (ref "P1") (pin "C21") (pinfunction "C21_C21") (pintype "passive"))
      (node (ref "P1") (pin "C24") (pinfunction "C24_C24") (pintype "passive"))
      (node (ref "P1") (pin "C25") (pinfunction "C25_C25") (pintype "passive"))
      (node (ref "P1") (pin "C28") (pinfunction "C28_C28") (pintype "passive"))
      (node (ref "P1") (pin "C29") (pinfunction "C29_C29") (pintype "passive"))
      (node (ref "P1") (pin "C32") (pinfunction "C32_C32") (pintype "passive"))
      (node (ref "P1") (pin "C33") (pinfunction "C33_C33") (pintype "passive"))
      (node (ref "P1") (pin "C36") (pinfunction "C36_C36") (pintype "passive"))
      (node (ref "P1") (pin "C38") (pinfunction "C38_C38") (pintype "passive"))
      (node (ref "P1") (pin "C4") (pinfunction "C4_C4") (pintype "passive"))
      (node (ref "P1") (pin "C40") (pinfunction "C40_C40") (pintype "passive"))
      (node (ref "P1") (pin "C5") (pinfunction "C5_C5") (pintype "passive"))
      (node (ref "P1") (pin "C8") (pinfunction "C8_C8") (pintype "passive"))
      (node (ref "P1") (pin "C9") (pinfunction "C9_C9") (pintype "passive"))
      (node (ref "P1") (pin "D10") (pinfunction "D10_D10") (pintype "passive"))
      (node (ref "P1") (pin "D13") (pinfunction "D13_D13") (pintype "passive"))
      (node (ref "P1") (pin "D16") (pinfunction "D16_D16") (pintype "passive"))
      (node (ref "P1") (pin "D19") (pinfunction "D19_D19") (pintype "passive"))
      (node (ref "P1") (pin "D2") (pinfunction "D2_D2") (pintype "passive"))
      (node (ref "P1") (pin "D22") (pinfunction "D22_D22") (pintype "passive"))
      (node (ref "P1") (pin "D25") (pinfunction "D25_D25") (pintype "passive"))
      (node (ref "P1") (pin "D28") (pinfunction "D28_D28") (pintype "passive"))
      (node (ref "P1") (pin "D3") (pinfunction "D3_D3") (pintype "passive"))
      (node (ref "P1") (pin "D37") (pinfunction "D37_D37") (pintype "passive"))
      (node (ref "P1") (pin "D39") (pinfunction "D39_D39") (pintype "passive"))
      (node (ref "P1") (pin "D6") (pinfunction "D6_D6") (pintype "passive"))
      (node (ref "P1") (pin "D7") (pinfunction "D7_D7") (pintype "passive"))
      (node (ref "P1") (pin "E1") (pinfunction "E1_E1") (pintype "passive"))
      (node (ref "P1") (pin "E11") (pinfunction "E11_E11") (pintype "passive"))
      (node (ref "P1") (pin "E14") (pinfunction "E14_E14") (pintype "passive"))
      (node (ref "P1") (pin "E17") (pinfunction "E17_E17") (pintype "passive"))
      (node (ref "P1") (pin "E20") (pinfunction "E20_E20") (pintype "passive"))
      (node (ref "P1") (pin "E23") (pinfunction "E23_E23") (pintype "passive"))
      (node (ref "P1") (pin "E26") (pinfunction "E26_E26") (pintype "passive"))
      (node (ref "P1") (pin "E29") (pinfunction "E29_E29") (pintype "passive"))
      (node (ref "P1") (pin "E32") (pinfunction "E32_E32") (pintype "passive"))
      (node (ref "P1") (pin "E35") (pinfunction "E35_E35") (pintype "passive"))
      (node (ref "P1") (pin "E38") (pinfunction "E38_E38") (pintype "passive"))
      (node (ref "P1") (pin "E4") (pinfunction "E4_E4") (pintype "passive"))
      (node (ref "P1") (pin "E40") (pinfunction "E40_E40") (pintype "passive"))
      (node (ref "P1") (pin "E5") (pinfunction "E5_E5") (pintype "passive"))
      (node (ref "P1") (pin "E8") (pinfunction "E8_E8") (pintype "passive"))
      (node (ref "P1") (pin "F12") (pinfunction "F12_F12") (pintype "passive"))
      (node (ref "P1") (pin "F15") (pinfunction "F15_F15") (pintype "passive"))
      (node (ref "P1") (pin "F18") (pinfunction "F18_F18") (pintype "passive"))
      (node (ref "P1") (pin "F2") (pinfunction "F2_F2") (pintype "passive"))
      (node (ref "P1") (pin "F21") (pinfunction "F21_F21") (pintype "passive"))
      (node (ref "P1") (pin "F24") (pinfunction "F24_F24") (pintype "passive"))
      (node (ref "P1") (pin "F27") (pinfunction "F27_F27") (pintype "passive"))
      (node (ref "P1") (pin "F3") (pinfunction "F3_F3") (pintype "passive"))
      (node (ref "P1") (pin "F30") (pinfunction "F30_F30") (pintype "passive"))
      (node (ref "P1") (pin "F33") (pinfunction "F33_F33") (pintype "passive"))
      (node (ref "P1") (pin "F36") (pinfunction "F36_F36") (pintype "passive"))
      (node (ref "P1") (pin "F39") (pinfunction "F39_F39") (pintype "passive"))
      (node (ref "P1") (pin "F6") (pinfunction "F6_F6") (pintype "passive"))
      (node (ref "P1") (pin "F9") (pinfunction "F9_F9") (pintype "passive"))
      (node (ref "P1") (pin "G1") (pinfunction "G1_G1") (pintype "passive"))
      (node (ref "P1") (pin "G11") (pinfunction "G11_G11") (pintype "passive"))
      (node (ref "P1") (pin "G14") (pinfunction "G14_G14") (pintype "passive"))
      (node (ref "P1") (pin "G17") (pinfunction "G17_G17") (pintype "passive"))
      (node (ref "P1") (pin "G20") (pinfunction "G20_G20") (pintype "passive"))
      (node (ref "P1") (pin "G23") (pinfunction "G23_G23") (pintype "passive"))
      (node (ref "P1") (pin "G26") (pinfunction "G26_G26") (pintype "passive"))
      (node (ref "P1") (pin "G29") (pinfunction "G29_G29") (pintype "passive"))
      (node (ref "P1") (pin "G32") (pinfunction "G32_G32") (pintype "passive"))
      (node (ref "P1") (pin "G35") (pinfunction "G35_G35") (pintype "passive"))
      (node (ref "P1") (pin "G38") (pinfunction "G38_G38") (pintype "passive"))
      (node (ref "P1") (pin "G4") (pinfunction "G4_G4") (pintype "passive"))
      (node (ref "P1") (pin "G40") (pinfunction "G40_G40") (pintype "passive"))
      (node (ref "P1") (pin "G5") (pinfunction "G5_G5") (pintype "passive"))
      (node (ref "P1") (pin "G8") (pinfunction "G8_G8") (pintype "passive"))
      (node (ref "P1") (pin "H12") (pinfunction "H12_H12") (pintype "passive"))
      (node (ref "P1") (pin "H15") (pinfunction "H15_H15") (pintype "passive"))
      (node (ref "P1") (pin "H18") (pinfunction "H18_H18") (pintype "passive"))
      (node (ref "P1") (pin "H21") (pinfunction "H21_H21") (pintype "passive"))
      (node (ref "P1") (pin "H24") (pinfunction "H24_H24") (pintype "passive"))
      (node (ref "P1") (pin "H27") (pinfunction "H27_H27") (pintype "passive"))
      (node (ref "P1") (pin "H3") (pinfunction "H3_H3") (pintype "passive"))
      (node (ref "P1") (pin "H30") (pinfunction "H30_H30") (pintype "passive"))
      (node (ref "P1") (pin "H33") (pinfunction "H33_H33") (pintype "passive"))
      (node (ref "P1") (pin "H36") (pinfunction "H36_H36") (pintype "passive"))
      (node (ref "P1") (pin "H39") (pinfunction "H39_H39") (pintype "passive"))
      (node (ref "P1") (pin "H6") (pinfunction "H6_H6") (pintype "passive"))
      (node (ref "P1") (pin "H9") (pinfunction "H9_H9") (pintype "passive"))
      (node (ref "P1") (pin "J1") (pinfunction "J1_J1") (pintype "passive"))
      (node (ref "P1") (pin "J11") (pinfunction "J11_J11") (pintype "passive"))
      (node (ref "P1") (pin "J14") (pinfunction "J14_J14") (pintype "passive"))
      (node (ref "P1") (pin "J17") (pinfunction "J17_J17") (pintype "passive"))
      (node (ref "P1") (pin "J20") (pinfunction "J20_J20") (pintype "passive"))
      (node (ref "P1") (pin "J23") (pinfunction "J23_J23") (pintype "passive"))
      (node (ref "P1") (pin "J26") (pinfunction "J26_J26") (pintype "passive"))
      (node (ref "P1") (pin "J29") (pinfunction "J29_J29") (pintype "passive"))
      (node (ref "P1") (pin "J32") (pinfunction "J32_J32") (pintype "passive"))
      (node (ref "P1") (pin "J35") (pinfunction "J35_J35") (pintype "passive"))
      (node (ref "P1") (pin "J38") (pinfunction "J38_J38") (pintype "passive"))
      (node (ref "P1") (pin "J4") (pinfunction "J4_J4") (pintype "passive"))
      (node (ref "P1") (pin "J40") (pinfunction "J40_J40") (pintype "passive"))
      (node (ref "P1") (pin "J5") (pinfunction "J5_J5") (pintype "passive"))
      (node (ref "P1") (pin "J8") (pinfunction "J8_J8") (pintype "passive"))
      (node (ref "P1") (pin "K12") (pinfunction "K12_K12") (pintype "passive"))
      (node (ref "P1") (pin "K15") (pinfunction "K15_K15") (pintype "passive"))
      (node (ref "P1") (pin "K18") (pinfunction "K18_K18") (pintype "passive"))
      (node (ref "P1") (pin "K2") (pinfunction "K2_K2") (pintype "passive"))
      (node (ref "P1") (pin "K21") (pinfunction "K21_K21") (pintype "passive"))
      (node (ref "P1") (pin "K24") (pinfunction "K24_K24") (pintype "passive"))
      (node (ref "P1") (pin "K27") (pinfunction "K27_K27") (pintype "passive"))
      (node (ref "P1") (pin "K3") (pinfunction "K3_K3") (pintype "passive"))
      (node (ref "P1") (pin "K30") (pinfunction "K30_K30") (pintype "passive"))
      (node (ref "P1") (pin "K33") (pinfunction "K33_K33") (pintype "passive"))
      (node (ref "P1") (pin "K36") (pinfunction "K36_K36") (pintype "passive"))
      (node (ref "P1") (pin "K39") (pinfunction "K39_K39") (pintype "passive"))
      (node (ref "P1") (pin "K6") (pinfunction "K6_K6") (pintype "passive"))
      (node (ref "P1") (pin "K9") (pinfunction "K9_K9") (pintype "passive"))
    )
    (net (code "116") (name "Net-(J1-PadA2)") (class "Default")
      (node (ref "J1") (pin "A2") (pinfunction "A2_A2") (pintype "passive"))
      (node (ref "P1") (pin "A2") (pinfunction "A2_A2") (pintype "passive"))
    )
    (net (code "117") (name "Net-(J1-PadA3)") (class "Default")
      (node (ref "J1") (pin "A3") (pinfunction "A3_A3") (pintype "passive"))
      (node (ref "P1") (pin "A3") (pinfunction "A3_A3") (pintype "passive"))
    )
    (net (code "118") (name "Net-(J1-PadA6)") (class "Default")
      (node (ref "J1") (pin "A6") (pinfunction "A6_A6") (pintype "passive"))
      (node (ref "P1") (pin "A6") (pinfunction "A6_A6") (pintype "passive"))
    )
    (net (code "119") (name "Net-(J1-PadA7)") (class "Default")
      (node (ref "J1") (pin "A7") (pinfunction "A7_A7") (pintype "passive"))
      (node (ref "P1") (pin "A7") (pinfunction "A7_A7") (pintype "passive"))
    )
    (net (code "120") (name "Net-(J1-PadA10)") (class "Default")
      (node (ref "J1") (pin "A10") (pinfunction "A10_A10") (pintype "passive"))
      (node (ref "P1") (pin "A10") (pinfunction "A10_A10") (pintype "passive"))
    )
    (net (code "121") (name "Net-(J1-PadA11)") (class "Default")
      (node (ref "J1") (pin "A11") (pinfunction "A11_A11") (pintype "passive"))
      (node (ref "P1") (pin "A11") (pinfunction "A11_A11") (pintype "passive"))
    )
    (net (code "122") (name "Net-(J1-PadA14)") (class "Default")
      (node (ref "J1") (pin "A14") (pinfunction "A14_A14") (pintype "passive"))
      (node (ref "P1") (pin "A14") (pinfunction "A14_A14") (pintype "passive"))
    )
    (net (code "123") (name "Net-(J1-PadA15)") (class "Default")
      (node (ref "J1") (pin "A15") (pinfunction "A15_A15") (pintype "passive"))
      (node (ref "P1") (pin "A15") (pinfunction "A15_A15") (pintype "passive"))
    )
    (net (code "124") (name "Net-(J1-PadA18)") (class "Default")
      (node (ref "J1") (pin "A18") (pinfunction "A18_A18") (pintype "passive"))
      (node (ref "P1") (pin "A18") (pinfunction "A18_A18") (pintype "passive"))
    )
    (net (code "125") (name "Net-(J1-PadA19)") (class "Default")
      (node (ref "J1") (pin "A19") (pinfunction "A19_A19") (pintype "passive"))
      (node (ref "P1") (pin "A19") (pinfunction "A19_A19") (pintype "passive"))
    )
    (net (code "126") (name "Net-(J1-PadA22)") (class "Default")
      (node (ref "J1") (pin "A22") (pinfunction "A22_A22") (pintype "passive"))
      (node (ref "P1") (pin "A22") (pinfunction "A22_A22") (pintype "passive"))
    )
    (net (code "127") (name "Net-(J1-PadA23)") (class "Default")
      (node (ref "J1") (pin "A23") (pinfunction "A23_A23") (pintype "passive"))
      (node (ref "P1") (pin "A23") (pinfunction "A23_A23") (pintype "passive"))
    )
    (net (code "128") (name "Net-(J1-PadA26)") (class "Default")
      (node (ref "J1") (pin "A26") (pinfunction "A26_A26") (pintype "passive"))
      (node (ref "P1") (pin "A26") (pinfunction "A26_A26") (pintype "passive"))
    )
    (net (code "129") (name "Net-(J1-PadA27)") (class "Default")
      (node (ref "J1") (pin "A27") (pinfunction "A27_A27") (pintype "passive"))
      (node (ref "P1") (pin "A27") (pinfunction "A27_A27") (pintype "passive"))
    )
    (net (code "130") (name "Net-(J1-PadA30)") (class "Default")
      (node (ref "J1") (pin "A30") (pinfunction "A30_A30") (pintype "passive"))
      (node (ref "P1") (pin "A30") (pinfunction "A30_A30") (pintype "passive"))
    )
    (net (code "131") (name "Net-(J1-PadA31)") (class "Default")
      (node (ref "J1") (pin "A31") (pinfunction "A31_A31") (pintype "passive"))
      (node (ref "P1") (pin "A31") (pinfunction "A31_A31") (pintype "passive"))
    )
    (net (code "132") (name "Net-(J1-PadA34)") (class "Default")
      (node (ref "J1") (pin "A34") (pinfunction "A34_A34") (pintype "passive"))
      (node (ref "P1") (pin "A34") (pinfunction "A34_A34") (pintype "passive"))
    )
    (net (code "133") (name "Net-(J1-PadA35)") (class "Default")
      (node (ref "J1") (pin "A35") (pinfunction "A35_A35") (pintype "passive"))
      (node (ref "P1") (pin "A35") (pinfunction "A35_A35") (pintype "passive"))
    )
    (net (code "134") (name "Net-(J1-PadA38)") (class "Default")
      (node (ref "J1") (pin "A38") (pinfunction "A38_A38") (pintype "passive"))
      (node (ref "P1") (pin "A38") (pinfunction "A38_A38") (pintype "passive"))
    )
    (net (code "135") (name "Net-(J1-PadA39)") (class "Default")
      (node (ref "J1") (pin "A39") (pinfunction "A39_A39") (pintype "passive"))
      (node (ref "P1") (pin "A39") (pinfunction "A39_A39") (pintype "passive"))
    )
    (net (code "136") (name "Net-(J1-PadB1)") (class "Default")
      (node (ref "J1") (pin "B1") (pinfunction "B1_B1") (pintype "passive"))
      (node (ref "P1") (pin "B1") (pinfunction "B1_B1") (pintype "passive"))
    )
    (net (code "137") (name "Net-(J1-PadB4)") (class "Default")
      (node (ref "J1") (pin "B4") (pinfunction "B4_B4") (pintype "passive"))
      (node (ref "P1") (pin "B4") (pinfunction "B4_B4") (pintype "passive"))
    )
    (net (code "138") (name "Net-(J1-PadB5)") (class "Default")
      (node (ref "J1") (pin "B5") (pinfunction "B5_B5") (pintype "passive"))
      (node (ref "P1") (pin "B5") (pinfunction "B5_B5") (pintype "passive"))
    )
    (net (code "139") (name "Net-(J1-PadB8)") (class "Default")
      (node (ref "J1") (pin "B8") (pinfunction "B8_B8") (pintype "passive"))
      (node (ref "P1") (pin "B8") (pinfunction "B8_B8") (pintype "passive"))
    )
    (net (code "140") (name "Net-(J1-PadB9)") (class "Default")
      (node (ref "J1") (pin "B9") (pinfunction "B9_B9") (pintype "passive"))
      (node (ref "P1") (pin "B9") (pinfunction "B9_B9") (pintype "passive"))
    )
    (net (code "141") (name "Net-(J1-PadB12)") (class "Default")
      (node (ref "J1") (pin "B12") (pinfunction "B12_B12") (pintype "passive"))
      (node (ref "P1") (pin "B12") (pinfunction "B12_B12") (pintype "passive"))
    )
    (net (code "142") (name "Net-(J1-PadB13)") (class "Default")
      (node (ref "J1") (pin "B13") (pinfunction "B13_B13") (pintype "passive"))
      (node (ref "P1") (pin "B13") (pinfunction "B13_B13") (pintype "passive"))
    )
    (net (code "143") (name "Net-(J1-PadB16)") (class "Default")
      (node (ref "J1") (pin "B16") (pinfunction "B16_B16") (pintype "passive"))
      (node (ref "P1") (pin "B16") (pinfunction "B16_B16") (pintype "passive"))
    )
    (net (code "144") (name "Net-(J1-PadB17)") (class "Default")
      (node (ref "J1") (pin "B17") (pinfunction "B17_B17") (pintype "passive"))
      (node (ref "P1") (pin "B17") (pinfunction "B17_B17") (pintype "passive"))
    )
    (net (code "145") (name "Net-(J1-PadB20)") (class "Default")
      (node (ref "J1") (pin "B20") (pinfunction "B20_B20") (pintype "passive"))
      (node (ref "P1") (pin "B20") (pinfunction "B20_B20") (pintype "passive"))
    )
    (net (code "146") (name "Net-(J1-PadB21)") (class "Default")
      (node (ref "J1") (pin "B21") (pinfunction "B21_B21") (pintype "passive"))
      (node (ref "P1") (pin "B21") (pinfunction "B21_B21") (pintype "passive"))
    )
    (net (code "147") (name "Net-(J1-PadB24)") (class "Default")
      (node (ref "J1") (pin "B24") (pinfunction "B24_B24") (pintype "passive"))
      (node (ref "P1") (pin "B24") (pinfunction "B24_B24") (pintype "passive"))
    )
    (net (code "148") (name "Net-(J1-PadB25)") (class "Default")
      (node (ref "J1") (pin "B25") (pinfunction "B25_B25") (pintype "passive"))
      (node (ref "P1") (pin "B25") (pinfunction "B25_B25") (pintype "passive"))
    )
    (net (code "149") (name "Net-(J1-PadB28)") (class "Default")
      (node (ref "J1") (pin "B28") (pinfunction "B28_B28") (pintype "passive"))
      (node (ref "P1") (pin "B28") (pinfunction "B28_B28") (pintype "passive"))
    )
    (net (code "150") (name "Net-(J1-PadB29)") (class "Default")
      (node (ref "J1") (pin "B29") (pinfunction "B29_B29") (pintype "passive"))
      (node (ref "P1") (pin "B29") (pinfunction "B29_B29") (pintype "passive"))
    )
    (net (code "151") (name "Net-(J1-PadB32)") (class "Default")
      (node (ref "J1") (pin "B32") (pinfunction "B32_B32") (pintype "passive"))
      (node (ref "P1") (pin "B32") (pinfunction "B32_B32") (pintype "passive"))
    )
    (net (code "152") (name "Net-(J1-PadB33)") (class "Default")
      (node (ref "J1") (pin "B33") (pinfunction "B33_B33") (pintype "passive"))
      (node (ref "P1") (pin "B33") (pinfunction "B33_B33") (pintype "passive"))
    )
    (net (code "153") (name "Net-(J1-PadB36)") (class "Default")
      (node (ref "J1") (pin "B36") (pinfunction "B36_B36") (pintype "passive"))
      (node (ref "P1") (pin "B36") (pinfunction "B36_B36") (pintype "passive"))
    )
    (net (code "154") (name "Net-(J1-PadB37)") (class "Default")
      (node (ref "J1") (pin "B37") (pinfunction "B37_B37") (pintype "passive"))
      (node (ref "P1") (pin "B37") (pinfunction "B37_B37") (pintype "passive"))
    )
    (net (code "155") (name "Net-(J1-PadB40)") (class "Default")
      (node (ref "J1") (pin "B40") (pinfunction "B40_B40") (pintype "passive"))
      (node (ref "P1") (pin "B40") (pinfunction "B40_B40") (pintype "passive"))
    )
    (net (code "156") (name "Net-(J1-PadC2)") (class "Default")
      (node (ref "J1") (pin "C2") (pinfunction "C2_C2") (pintype "passive"))
      (node (ref "P1") (pin "C2") (pinfunction "C2_C2") (pintype "passive"))
    )
    (net (code "157") (name "Net-(J1-PadC3)") (class "Default")
      (node (ref "J1") (pin "C3") (pinfunction "C3_C3") (pintype "passive"))
      (node (ref "P1") (pin "C3") (pinfunction "C3_C3") (pintype "passive"))
    )
    (net (code "158") (name "Net-(J1-PadC6)") (class "Default")
      (node (ref "J1") (pin "C6") (pinfunction "C6_C6") (pintype "passive"))
      (node (ref "P1") (pin "C6") (pinfunction "C6_C6") (pintype "passive"))
    )
    (net (code "159") (name "Net-(J1-PadC7)") (class "Default")
      (node (ref "J1") (pin "C7") (pinfunction "C7_C7") (pintype "passive"))
      (node (ref "P1") (pin "C7") (pinfunction "C7_C7") (pintype "passive"))
    )
    (net (code "160") (name "Net-(J1-PadC30)") (class "Default")
      (node (ref "J1") (pin "C30") (pinfunction "C30_C30") (pintype "passive"))
      (node (ref "P1") (pin "C30") (pinfunction "C30_C30") (pintype "passive"))
    )
    (net (code "161") (name "Net-(J1-PadC31)") (class "Default")
      (node (ref "J1") (pin "C31") (pinfunction "C31_C31") (pintype "passive"))
      (node (ref "P1") (pin "C31") (pinfunction "C31_C31") (pintype "passive"))
    )
    (net (code "162") (name "Net-(J1-PadC34)") (class "Default")
      (node (ref "J1") (pin "C34") (pinfunction "C34_C34") (pintype "passive"))
      (node (ref "P1") (pin "C34") (pinfunction "C34_C34") (pintype "passive"))
    )
    (net (code "163") (name "Net-(J1-PadD1)") (class "Default")
      (node (ref "J1") (pin "D1") (pinfunction "D1_D1") (pintype "passive"))
      (node (ref "P1") (pin "D1") (pinfunction "D1_D1") (pintype "passive"))
    )
    (net (code "164") (name "Net-(J1-PadD4)") (class "Default")
      (node (ref "J1") (pin "D4") (pinfunction "D4_D4") (pintype "passive"))
      (node (ref "P1") (pin "D4") (pinfunction "D4_D4") (pintype "passive"))
    )
    (net (code "165") (name "Net-(J1-PadD5)") (class "Default")
      (node (ref "J1") (pin "D5") (pinfunction "D5_D5") (pintype "passive"))
      (node (ref "P1") (pin "D5") (pinfunction "D5_D5") (pintype "passive"))
    )
    (net (code "166") (name "Net-(J1-PadD29)") (class "Default")
      (node (ref "J1") (pin "D29") (pinfunction "D29_D29") (pintype "passive"))
      (node (ref "P1") (pin "D29") (pinfunction "D29_D29") (pintype "passive"))
    )
    (net (code "167") (name "Net-(J1-PadD30)") (class "Default")
      (node (ref "J1") (pin "D30") (pinfunction "D30_D30") (pintype "passive"))
      (node (ref "P1") (pin "D30") (pinfunction "D30_D30") (pintype "passive"))
    )
    (net (code "168") (name "Net-(J1-PadD31)") (class "Default")
      (node (ref "J1") (pin "D31") (pinfunction "D31_D31") (pintype "passive"))
      (node (ref "P1") (pin "D31") (pinfunction "D31_D31") (pintype "passive"))
    )
    (net (code "169") (name "Net-(J1-PadD32)") (class "Default")
      (node (ref "J1") (pin "D32") (pinfunction "D32_D32") (pintype "passive"))
      (node (ref "P1") (pin "D32") (pinfunction "D32_D32") (pintype "passive"))
    )
    (net (code "170") (name "Net-(J1-PadD33)") (class "Default")
      (node (ref "J1") (pin "D33") (pinfunction "D33_D33") (pintype "passive"))
      (node (ref "P1") (pin "D33") (pinfunction "D33_D33") (pintype "passive"))
    )
    (net (code "171") (name "Net-(J1-PadD34)") (class "Default")
      (node (ref "J1") (pin "D34") (pinfunction "D34_D34") (pintype "passive"))
      (node (ref "P1") (pin "D34") (pinfunction "D34_D34") (pintype "passive"))
    )
    (net (code "172") (name "Net-(J1-PadD35)") (class "Default")
      (node (ref "J1") (pin "D35") (pinfunction "D35_D35") (pintype "passive"))
      (node (ref "P1") (pin "D35") (pinfunction "D35_D35") (pintype "passive"))
    )
    (net (code "173") (name "Net-(J1-PadE2)") (class "Default")
      (node (ref "J1") (pin "E2") (pinfunction "E2_E2") (pintype "passive"))
      (node (ref "P1") (pin "E2") (pinfunction "E2_E2") (pintype "passive"))
    )
    (net (code "174") (name "Net-(J1-PadE3)") (class "Default")
      (node (ref "J1") (pin "E3") (pinfunction "E3_E3") (pintype "passive"))
      (node (ref "P1") (pin "E3") (pinfunction "E3_E3") (pintype "passive"))
    )
    (net (code "175") (name "Net-(J1-PadE6)") (class "Default")
      (node (ref "J1") (pin "E6") (pinfunction "E6_E6") (pintype "passive"))
      (node (ref "P1") (pin "E6") (pinfunction "E6_E6") (pintype "passive"))
    )
    (net (code "176") (name "Net-(J1-PadE7)") (class "Default")
      (node (ref "J1") (pin "E7") (pinfunction "E7_E7") (pintype "passive"))
      (node (ref "P1") (pin "E7") (pinfunction "E7_E7") (pintype "passive"))
    )
    (net (code "177") (name "Net-(J1-PadE9)") (class "Default")
      (node (ref "J1") (pin "E9") (pinfunction "E9_E9") (pintype "passive"))
      (node (ref "P1") (pin "E9") (pinfunction "E9_E9") (pintype "passive"))
    )
    (net (code "178") (name "Net-(J1-PadE10)") (class "Default")
      (node (ref "J1") (pin "E10") (pinfunction "E10_E10") (pintype "passive"))
      (node (ref "P1") (pin "E10") (pinfunction "E10_E10") (pintype "passive"))
    )
    (net (code "179") (name "Net-(J1-PadE12)") (class "Default")
      (node (ref "J1") (pin "E12") (pinfunction "E12_E12") (pintype "passive"))
      (node (ref "P1") (pin "E12") (pinfunction "E12_E12") (pintype "passive"))
    )
    (net (code "180") (name "Net-(J1-PadE13)") (class "Default")
      (node (ref "J1") (pin "E13") (pinfunction "E13_E13") (pintype "passive"))
      (node (ref "P1") (pin "E13") (pinfunction "E13_E13") (pintype "passive"))
    )
    (net (code "181") (name "Net-(J1-PadE15)") (class "Default")
      (node (ref "J1") (pin "E15") (pinfunction "E15_E15") (pintype "passive"))
      (node (ref "P1") (pin "E15") (pinfunction "E15_E15") (pintype "passive"))
    )
    (net (code "182") (name "Net-(J1-PadE16)") (class "Default")
      (node (ref "J1") (pin "E16") (pinfunction "E16_E16") (pintype "passive"))
      (node (ref "P1") (pin "E16") (pinfunction "E16_E16") (pintype "passive"))
    )
    (net (code "183") (name "Net-(J1-PadE18)") (class "Default")
      (node (ref "J1") (pin "E18") (pinfunction "E18_E18") (pintype "passive"))
      (node (ref "P1") (pin "E18") (pinfunction "E18_E18") (pintype "passive"))
    )
    (net (code "184") (name "Net-(J1-PadE19)") (class "Default")
      (node (ref "J1") (pin "E19") (pinfunction "E19_E19") (pintype "passive"))
      (node (ref "P1") (pin "E19") (pinfunction "E19_E19") (pintype "passive"))
    )
    (net (code "185") (name "Net-(J1-PadE21)") (class "Default")
      (node (ref "J1") (pin "E21") (pinfunction "E21_E21") (pintype "passive"))
      (node (ref "P1") (pin "E21") (pinfunction "E21_E21") (pintype "passive"))
    )
    (net (code "186") (name "Net-(J1-PadE22)") (class "Default")
      (node (ref "J1") (pin "E22") (pinfunction "E22_E22") (pintype "passive"))
      (node (ref "P1") (pin "E22") (pinfunction "E22_E22") (pintype "passive"))
    )
    (net (code "187") (name "Net-(J1-PadE24)") (class "Default")
      (node (ref "J1") (pin "E24") (pinfunction "E24_E24") (pintype "passive"))
      (node (ref "P1") (pin "E24") (pinfunction "E24_E24") (pintype "passive"))
    )
    (net (code "188") (name "Net-(J1-PadE25)") (class "Default")
      (node (ref "J1") (pin "E25") (pinfunction "E25_E25") (pintype "passive"))
      (node (ref "P1") (pin "E25") (pinfunction "E25_E25") (pintype "passive"))
    )
    (net (code "189") (name "Net-(J1-PadE27)") (class "Default")
      (node (ref "J1") (pin "E27") (pinfunction "E27_E27") (pintype "passive"))
      (node (ref "P1") (pin "E27") (pinfunction "E27_E27") (pintype "passive"))
    )
    (net (code "190") (name "Net-(J1-PadE28)") (class "Default")
      (node (ref "J1") (pin "E28") (pinfunction "E28_E28") (pintype "passive"))
      (node (ref "P1") (pin "E28") (pinfunction "E28_E28") (pintype "passive"))
    )
    (net (code "191") (name "Net-(J1-PadE30)") (class "Default")
      (node (ref "J1") (pin "E30") (pinfunction "E30_E30") (pintype "passive"))
      (node (ref "P1") (pin "E30") (pinfunction "E30_E30") (pintype "passive"))
    )
    (net (code "192") (name "Net-(J1-PadE31)") (class "Default")
      (node (ref "J1") (pin "E31") (pinfunction "E31_E31") (pintype "passive"))
      (node (ref "P1") (pin "E31") (pinfunction "E31_E31") (pintype "passive"))
    )
    (net (code "193") (name "Net-(J1-PadE33)") (class "Default")
      (node (ref "J1") (pin "E33") (pinfunction "E33_E33") (pintype "passive"))
      (node (ref "P1") (pin "E33") (pinfunction "E33_E33") (pintype "passive"))
    )
    (net (code "194") (name "Net-(J1-PadE34)") (class "Default")
      (node (ref "J1") (pin "E34") (pinfunction "E34_E34") (pintype "passive"))
      (node (ref "P1") (pin "E34") (pinfunction "E34_E34") (pintype "passive"))
    )
    (net (code "195") (name "Net-(J1-PadE36)") (class "Default")
      (node (ref "J1") (pin "E36") (pinfunction "E36_E36") (pintype "passive"))
      (node (ref "P1") (pin "E36") (pinfunction "E36_E36") (pintype "passive"))
    )
    (net (code "196") (name "Net-(J1-PadE37)") (class "Default")
      (node (ref "J1") (pin "E37") (pinfunction "E37_E37") (pintype "passive"))
      (node (ref "P1") (pin "E37") (pinfunction "E37_E37") (pintype "passive"))
    )
    (net (code "197") (name "Net-(J1-PadF1)") (class "Default")
      (node (ref "J1") (pin "F1") (pinfunction "F1_F1") (pintype "passive"))
      (node (ref "P1") (pin "F1") (pinfunction "F1_F1") (pintype "passive"))
    )
    (net (code "198") (name "Net-(J1-PadF4)") (class "Default")
      (node (ref "J1") (pin "F4") (pinfunction "F4_F4") (pintype "passive"))
      (node (ref "P1") (pin "F4") (pinfunction "F4_F4") (pintype "passive"))
    )
    (net (code "199") (name "Net-(J1-PadF5)") (class "Default")
      (node (ref "J1") (pin "F5") (pinfunction "F5_F5") (pintype "passive"))
      (node (ref "P1") (pin "F5") (pinfunction "F5_F5") (pintype "passive"))
    )
    (net (code "200") (name "Net-(J1-PadF7)") (class "Default")
      (node (ref "J1") (pin "F7") (pinfunction "F7_F7") (pintype "passive"))
      (node (ref "P1") (pin "F7") (pinfunction "F7_F7") (pintype "passive"))
    )
    (net (code "201") (name "Net-(J1-PadF8)") (class "Default")
      (node (ref "J1") (pin "F8") (pinfunction "F8_F8") (pintype "passive"))
      (node (ref "P1") (pin "F8") (pinfunction "F8_F8") (pintype "passive"))
    )
    (net (code "202") (name "Net-(J1-PadF10)") (class "Default")
      (node (ref "J1") (pin "F10") (pinfunction "F10_F10") (pintype "passive"))
      (node (ref "P1") (pin "F10") (pinfunction "F10_F10") (pintype "passive"))
    )
    (net (code "203") (name "Net-(J1-PadF11)") (class "Default")
      (node (ref "J1") (pin "F11") (pinfunction "F11_F11") (pintype "passive"))
      (node (ref "P1") (pin "F11") (pinfunction "F11_F11") (pintype "passive"))
    )
    (net (code "204") (name "Net-(J1-PadF13)") (class "Default")
      (node (ref "J1") (pin "F13") (pinfunction "F13_F13") (pintype "passive"))
      (node (ref "P1") (pin "F13") (pinfunction "F13_F13") (pintype "passive"))
    )
    (net (code "205") (name "Net-(J1-PadF14)") (class "Default")
      (node (ref "J1") (pin "F14") (pinfunction "F14_F14") (pintype "passive"))
      (node (ref "P1") (pin "F14") (pinfunction "F14_F14") (pintype "passive"))
    )
    (net (code "206") (name "Net-(J1-PadF16)") (class "Default")
      (node (ref "J1") (pin "F16") (pinfunction "F16_F16") (pintype "passive"))
      (node (ref "P1") (pin "F16") (pinfunction "F16_F16") (pintype "passive"))
    )
    (net (code "207") (name "Net-(J1-PadF17)") (class "Default")
      (node (ref "J1") (pin "F17") (pinfunction "F17_F17") (pintype "passive"))
      (node (ref "P1") (pin "F17") (pinfunction "F17_F17") (pintype "passive"))
    )
    (net (code "208") (name "Net-(J1-PadF19)") (class "Default")
      (node (ref "J1") (pin "F19") (pinfunction "F19_F19") (pintype "passive"))
      (node (ref "P1") (pin "F19") (pinfunction "F19_F19") (pintype "passive"))
    )
    (net (code "209") (name "Net-(J1-PadF20)") (class "Default")
      (node (ref "J1") (pin "F20") (pinfunction "F20_F20") (pintype "passive"))
      (node (ref "P1") (pin "F20") (pinfunction "F20_F20") (pintype "passive"))
    )
    (net (code "210") (name "Net-(J1-PadF22)") (class "Default")
      (node (ref "J1") (pin "F22") (pinfunction "F22_F22") (pintype "passive"))
      (node (ref "P1") (pin "F22") (pinfunction "F22_F22") (pintype "passive"))
    )
    (net (code "211") (name "Net-(J1-PadF23)") (class "Default")
      (node (ref "J1") (pin "F23") (pinfunction "F23_F23") (pintype "passive"))
      (node (ref "P1") (pin "F23") (pinfunction "F23_F23") (pintype "passive"))
    )
    (net (code "212") (name "Net-(J1-PadF25)") (class "Default")
      (node (ref "J1") (pin "F25") (pinfunction "F25_F25") (pintype "passive"))
      (node (ref "P1") (pin "F25") (pinfunction "F25_F25") (pintype "passive"))
    )
    (net (code "213") (name "Net-(J1-PadF26)") (class "Default")
      (node (ref "J1") (pin "F26") (pinfunction "F26_F26") (pintype "passive"))
      (node (ref "P1") (pin "F26") (pinfunction "F26_F26") (pintype "passive"))
    )
    (net (code "214") (name "Net-(J1-PadF28)") (class "Default")
      (node (ref "J1") (pin "F28") (pinfunction "F28_F28") (pintype "passive"))
      (node (ref "P1") (pin "F28") (pinfunction "F28_F28") (pintype "passive"))
    )
    (net (code "215") (name "Net-(J1-PadF29)") (class "Default")
      (node (ref "J1") (pin "F29") (pinfunction "F29_F29") (pintype "passive"))
      (node (ref "P1") (pin "F29") (pinfunction "F29_F29") (pintype "passive"))
    )
    (net (code "216") (name "Net-(J1-PadF31)") (class "Default")
      (node (ref "J1") (pin "F31") (pinfunction "F31_F31") (pintype "passive"))
      (node (ref "P1") (pin "F31") (pinfunction "F31_F31") (pintype "passive"))
    )
    (net (code "217") (name "Net-(J1-PadF32)") (class "Default")
      (node (ref "J1") (pin "F32") (pinfunction "F32_F32") (pintype "passive"))
      (node (ref "P1") (pin "F32") (pinfunction "F32_F32") (pintype "passive"))
    )
    (net (code "218") (name "Net-(J1-PadF34)") (class "Default")
      (node (ref "J1") (pin "F34") (pinfunction "F34_F34") (pintype "passive"))
      (node (ref "P1") (pin "F34") (pinfunction "F34_F34") (pintype "passive"))
    )
    (net (code "219") (name "Net-(J1-PadF35)") (class "Default")
      (node (ref "J1") (pin "F35") (pinfunction "F35_F35") (pintype "passive"))
      (node (ref "P1") (pin "F35") (pinfunction "F35_F35") (pintype "passive"))
    )
    (net (code "220") (name "Net-(J1-PadF37)") (class "Default")
      (node (ref "J1") (pin "F37") (pinfunction "F37_F37") (pintype "passive"))
      (node (ref "P1") (pin "F37") (pinfunction "F37_F37") (pintype "passive"))
    )
    (net (code "221") (name "Net-(J1-PadF38)") (class "Default")
      (node (ref "J1") (pin "F38") (pinfunction "F38_F38") (pintype "passive"))
      (node (ref "P1") (pin "F38") (pinfunction "F38_F38") (pintype "passive"))
    )
    (net (code "222") (name "Net-(J1-PadG2)") (class "Default")
      (node (ref "J1") (pin "G2") (pinfunction "G2_G2") (pintype "passive"))
      (node (ref "P1") (pin "G2") (pinfunction "G2_G2") (pintype "passive"))
    )
    (net (code "223") (name "Net-(J1-PadG3)") (class "Default")
      (node (ref "J1") (pin "G3") (pinfunction "G3_G3") (pintype "passive"))
      (node (ref "P1") (pin "G3") (pinfunction "G3_G3") (pintype "passive"))
    )
    (net (code "224") (name "Net-(J1-PadH1)") (class "Default")
      (node (ref "J1") (pin "H1") (pinfunction "H1_H1") (pintype "passive"))
      (node (ref "P1") (pin "H1") (pinfunction "H1_H1") (pintype "passive"))
    )
    (net (code "225") (name "Net-(J1-PadH2)") (class "Default")
      (node (ref "J1") (pin "H2") (pinfunction "H2_H2") (pintype "passive"))
      (node (ref "P1") (pin "H2") (pinfunction "H2_H2") (pintype "passive"))
    )
    (net (code "226") (name "Net-(J1-PadH4)") (class "Default")
      (node (ref "J1") (pin "H4") (pinfunction "H4_H4") (pintype "passive"))
      (node (ref "P1") (pin "H4") (pinfunction "H4_H4") (pintype "passive"))
    )
    (net (code "227") (name "Net-(J1-PadH5)") (class "Default")
      (node (ref "J1") (pin "H5") (pinfunction "H5_H5") (pintype "passive"))
      (node (ref "P1") (pin "H5") (pinfunction "H5_H5") (pintype "passive"))
    )
    (net (code "228") (name "Net-(J1-PadJ2)") (class "Default")
      (node (ref "J1") (pin "J2") (pinfunction "J2_J2") (pintype "passive"))
      (node (ref "P1") (pin "J2") (pinfunction "J2_J2") (pintype "passive"))
    )
    (net (code "229") (name "Net-(J1-PadJ3)") (class "Default")
      (node (ref "J1") (pin "J3") (pinfunction "J3_J3") (pintype "passive"))
      (node (ref "P1") (pin "J3") (pinfunction "J3_J3") (pintype "passive"))
    )
    (net (code "230") (name "Net-(J1-PadJ18)") (class "Default")
      (node (ref "J1") (pin "J18") (pinfunction "J18_J18") (pintype "passive"))
      (node (ref "P1") (pin "J18") (pinfunction "J18_J18") (pintype "passive"))
    )
    (net (code "231") (name "Net-(J1-PadJ19)") (class "Default")
      (node (ref "J1") (pin "J19") (pinfunction "J19_J19") (pintype "passive"))
      (node (ref "P1") (pin "J19") (pinfunction "J19_J19") (pintype "passive"))
    )
    (net (code "232") (name "Net-(J1-PadJ21)") (class "Default")
      (node (ref "J1") (pin "J21") (pinfunction "J21_J21") (pintype "passive"))
      (node (ref "P1") (pin "J21") (pinfunction "J21_J21") (pintype "passive"))
    )
    (net (code "233") (name "Net-(J1-PadJ22)") (class "Default")
      (node (ref "J1") (pin "J22") (pinfunction "J22_J22") (pintype "passive"))
      (node (ref "P1") (pin "J22") (pinfunction "J22_J22") (pintype "passive"))
    )
    (net (code "234") (name "Net-(J1-PadJ24)") (class "Default")
      (node (ref "J1") (pin "J24") (pinfunction "J24_J24") (pintype "passive"))
      (node (ref "P1") (pin "J24") (pinfunction "J24_J24") (pintype "passive"))
    )
    (net (code "235") (name "Net-(J1-PadJ25)") (class "Default")
      (node (ref "J1") (pin "J25") (pinfunction "J25_J25") (pintype "passive"))
      (node (ref "P1") (pin "J25") (pinfunction "J25_J25") (pintype "passive"))
    )
    (net (code "236") (name "Net-(J1-PadJ27)") (class "Default")
      (node (ref "J1") (pin "J27") (pinfunction "J27_J27") (pintype "passive"))
      (node (ref "P1") (pin "J27") (pinfunction "J27_J27") (pintype "passive"))
    )
    (net (code "237") (name "Net-(J1-PadJ28)") (class "Default")
      (node (ref "J1") (pin "J28") (pinfunction "J28_J28") (pintype "passive"))
      (node (ref "P1") (pin "J28") (pinfunction "J28_J28") (pintype "passive"))
    )
    (net (code "238") (name "Net-(J1-PadJ30)") (class "Default")
      (node (ref "J1") (pin "J30") (pinfunction "J30_J30") (pintype "passive"))
      (node (ref "P1") (pin "J30") (pinfunction "J30_J30") (pintype "passive"))
    )
    (net (code "239") (name "Net-(J1-PadJ31)") (class "Default")
      (node (ref "J1") (pin "J31") (pinfunction "J31_J31") (pintype "passive"))
      (node (ref "P1") (pin "J31") (pinfunction "J31_J31") (pintype "passive"))
    )
    (net (code "240") (name "Net-(J1-PadJ33)") (class "Default")
      (node (ref "J1") (pin "J33") (pinfunction "J33_J33") (pintype "passive"))
      (node (ref "P1") (pin "J33") (pinfunction "J33_J33") (pintype "passive"))
    )
    (net (code "241") (name "Net-(J1-PadJ34)") (class "Default")
      (node (ref "J1") (pin "J34") (pinfunction "J34_J34") (pintype "passive"))
      (node (ref "P1") (pin "J34") (pinfunction "J34_J34") (pintype "passive"))
    )
    (net (code "242") (name "Net-(J1-PadJ36)") (class "Default")
      (node (ref "J1") (pin "J36") (pinfunction "J36_J36") (pintype "passive"))
      (node (ref "P1") (pin "J36") (pinfunction "J36_J36") (pintype "passive"))
    )
    (net (code "243") (name "Net-(J1-PadJ37)") (class "Default")
      (node (ref "J1") (pin "J37") (pinfunction "J37_J37") (pintype "passive"))
      (node (ref "P1") (pin "J37") (pinfunction "J37_J37") (pintype "passive"))
    )
    (net (code "244") (name "Net-(J1-PadJ39)") (class "Default")
      (node (ref "J1") (pin "J39") (pinfunction "J39_J39") (pintype "passive"))
      (node (ref "P1") (pin "J39") (pinfunction "J39_J39") (pintype "passive"))
    )
    (net (code "245") (name "Net-(J1-PadK1)") (class "Default")
      (node (ref "J1") (pin "K1") (pinfunction "K1_K1") (pintype "passive"))
      (node (ref "P1") (pin "K1") (pinfunction "K1_K1") (pintype "passive"))
    )
    (net (code "246") (name "Net-(J1-PadK4)") (class "Default")
      (node (ref "J1") (pin "K4") (pinfunction "K4_K4") (pintype "passive"))
      (node (ref "P1") (pin "K4") (pinfunction "K4_K4") (pintype "passive"))
    )
    (net (code "247") (name "Net-(J1-PadK5)") (class "Default")
      (node (ref "J1") (pin "K5") (pinfunction "K5_K5") (pintype "passive"))
      (node (ref "P1") (pin "K5") (pinfunction "K5_K5") (pintype "passive"))
    )
    (net (code "248") (name "Net-(J1-PadK19)") (class "Default")
      (node (ref "J1") (pin "K19") (pinfunction "K19_K19") (pintype "passive"))
      (node (ref "P1") (pin "K19") (pinfunction "K19_K19") (pintype "passive"))
    )
    (net (code "249") (name "Net-(J1-PadK20)") (class "Default")
      (node (ref "J1") (pin "K20") (pinfunction "K20_K20") (pintype "passive"))
      (node (ref "P1") (pin "K20") (pinfunction "K20_K20") (pintype "passive"))
    )
    (net (code "250") (name "Net-(J1-PadK22)") (class "Default")
      (node (ref "J1") (pin "K22") (pinfunction "K22_K22") (pintype "passive"))
      (node (ref "P1") (pin "K22") (pinfunction "K22_K22") (pintype "passive"))
    )
    (net (code "251") (name "Net-(J1-PadK23)") (class "Default")
      (node (ref "J1") (pin "K23") (pinfunction "K23_K23") (pintype "passive"))
      (node (ref "P1") (pin "K23") (pinfunction "K23_K23") (pintype "passive"))
    )
    (net (code "252") (name "Net-(J1-PadK25)") (class "Default")
      (node (ref "J1") (pin "K25") (pinfunction "K25_K25") (pintype "passive"))
      (node (ref "P1") (pin "K25") (pinfunction "K25_K25") (pintype "passive"))
    )
    (net (code "253") (name "Net-(J1-PadK26)") (class "Default")
      (node (ref "J1") (pin "K26") (pinfunction "K26_K26") (pintype "passive"))
      (node (ref "P1") (pin "K26") (pinfunction "K26_K26") (pintype "passive"))
    )
    (net (code "254") (name "Net-(J1-PadK28)") (class "Default")
      (node (ref "J1") (pin "K28") (pinfunction "K28_K28") (pintype "passive"))
      (node (ref "P1") (pin "K28") (pinfunction "K28_K28") (pintype "passive"))
    )
    (net (code "255") (name "Net-(J1-PadK29)") (class "Default")
      (node (ref "J1") (pin "K29") (pinfunction "K29_K29") (pintype "passive"))
      (node (ref "P1") (pin "K29") (pinfunction "K29_K29") (pintype "passive"))
    )
    (net (code "256") (name "Net-(J1-PadK31)") (class "Default")
      (node (ref "J1") (pin "K31") (pinfunction "K31_K31") (pintype "passive"))
      (node (ref "P1") (pin "K31") (pinfunction "K31_K31") (pintype "passive"))
    )
    (net (code "257") (name "Net-(J1-PadK32)") (class "Default")
      (node (ref "J1") (pin "K32") (pinfunction "K32_K32") (pintype "passive"))
      (node (ref "P1") (pin "K32") (pinfunction "K32_K32") (pintype "passive"))
    )
    (net (code "258") (name "Net-(J1-PadK34)") (class "Default")
      (node (ref "J1") (pin "K34") (pinfunction "K34_K34") (pintype "passive"))
      (node (ref "P1") (pin "K34") (pinfunction "K34_K34") (pintype "passive"))
    )
    (net (code "259") (name "Net-(J1-PadK35)") (class "Default")
      (node (ref "J1") (pin "K35") (pinfunction "K35_K35") (pintype "passive"))
      (node (ref "P1") (pin "K35") (pinfunction "K35_K35") (pintype "passive"))
    )
    (net (code "260") (name "Net-(J1-PadK37)") (class "Default")
      (node (ref "J1") (pin "K37") (pinfunction "K37_K37") (pintype "passive"))
      (node (ref "P1") (pin "K37") (pinfunction "K37_K37") (pintype "passive"))
    )
    (net (code "261") (name "Net-(J1-PadK38)") (class "Default")
      (node (ref "J1") (pin "K38") (pinfunction "K38_K38") (pintype "passive"))
      (node (ref "P1") (pin "K38") (pinfunction "K38_K38") (pintype "passive"))
    )
    (net (code "262") (name "Net-(J1-PadK40)") (class "Default")
      (node (ref "J1") (pin "K40") (pinfunction "K40_K40") (pintype "passive"))
      (node (ref "P1") (pin "K40") (pinfunction "K40_K40") (pintype "passive"))
    )
  )
)
